# SCH_Nucleo__V3_2022-10-20.net
KiCad netlist of a schematic drawn in EasyEDA
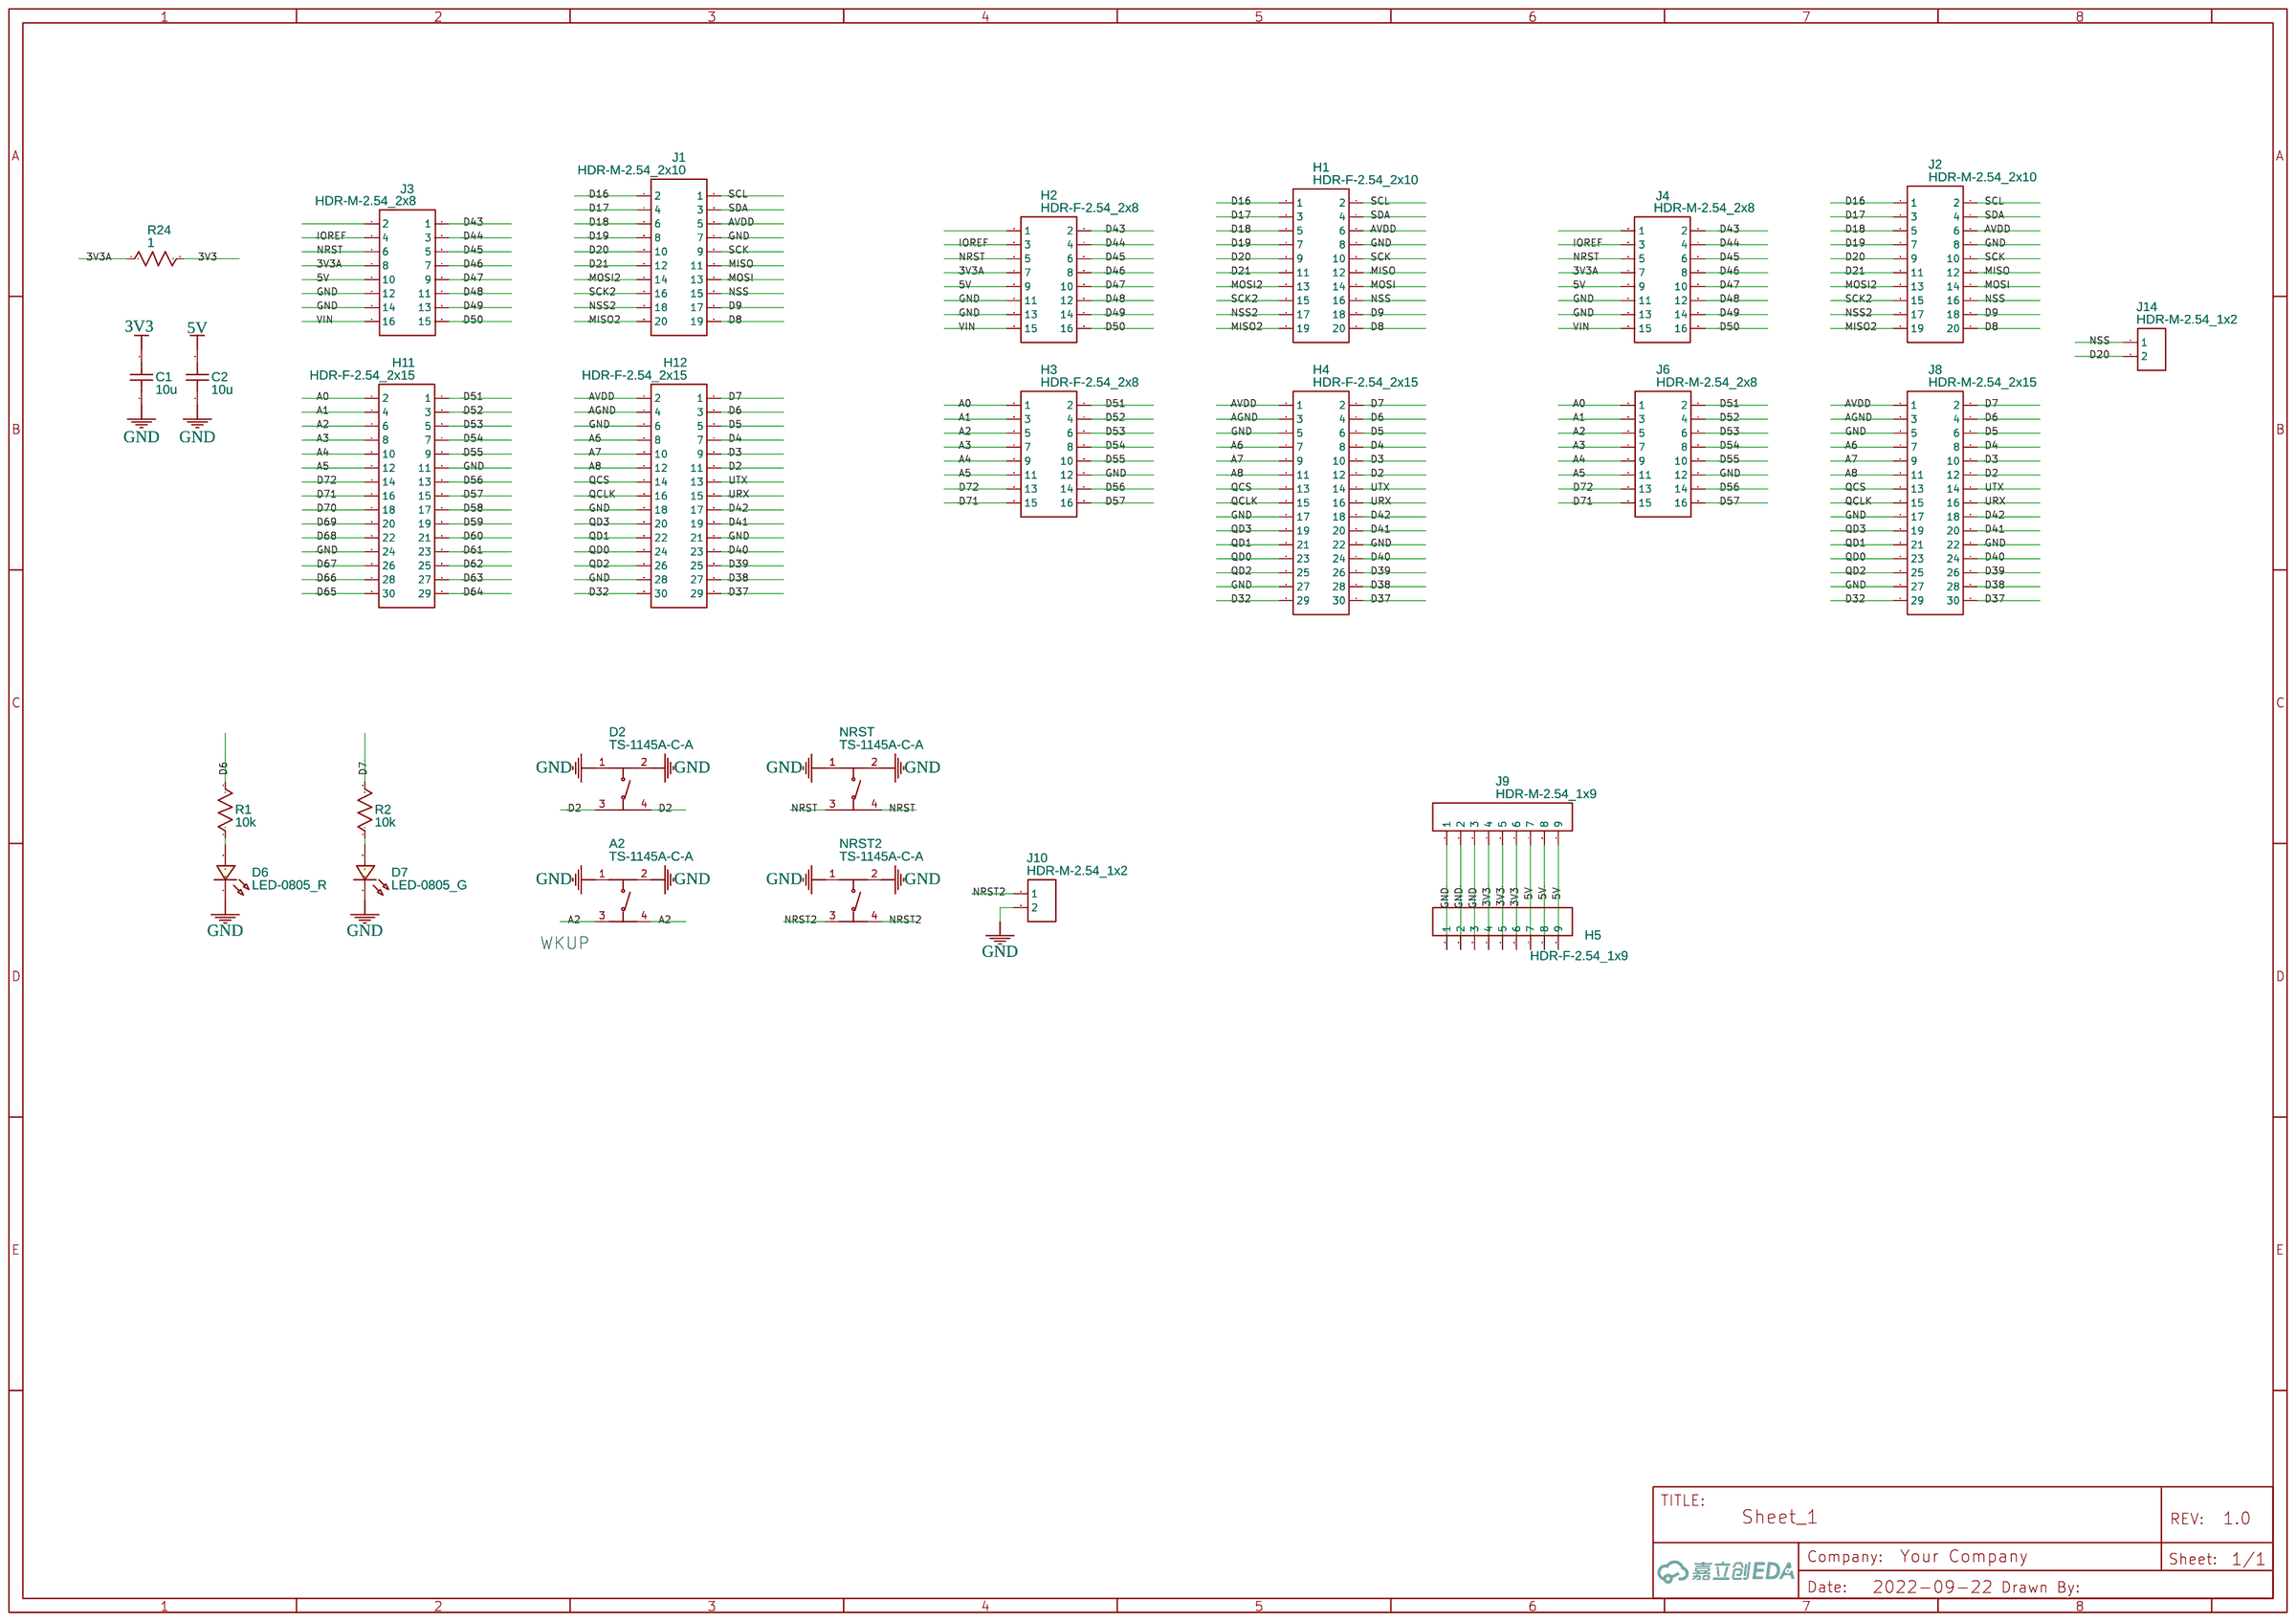
[diagram p0: 连接器]
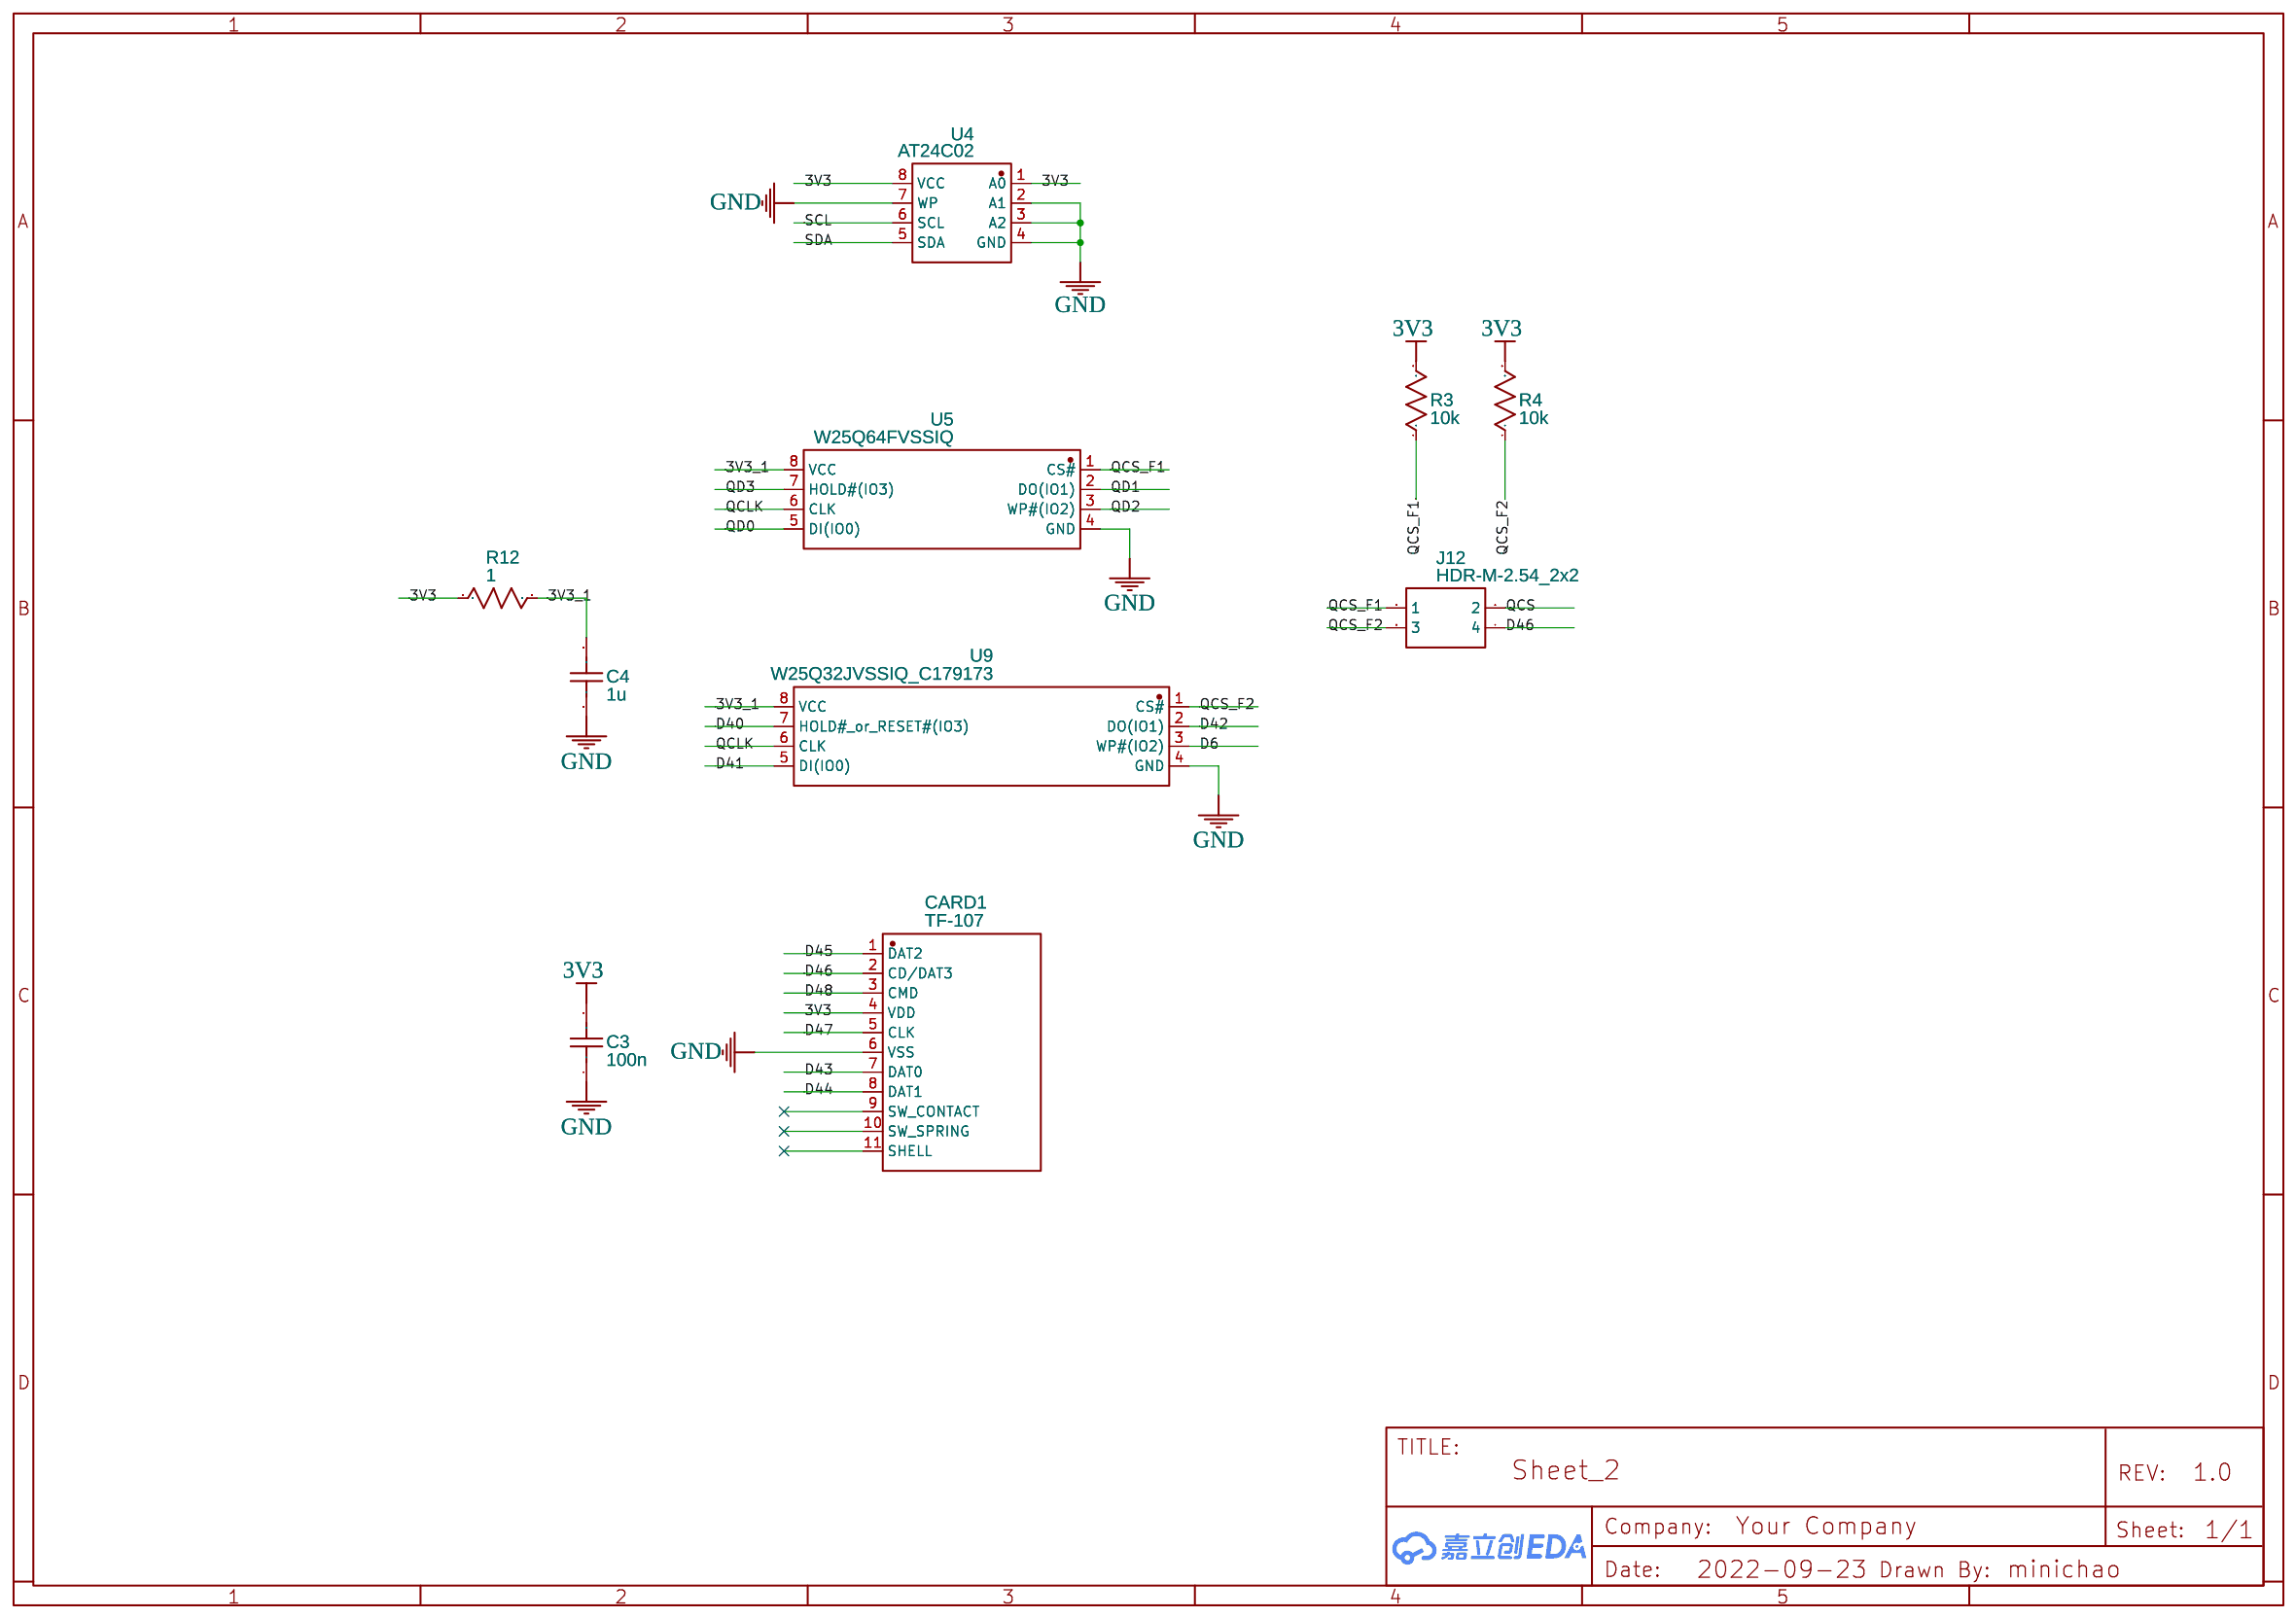
[diagram p1: 存储]
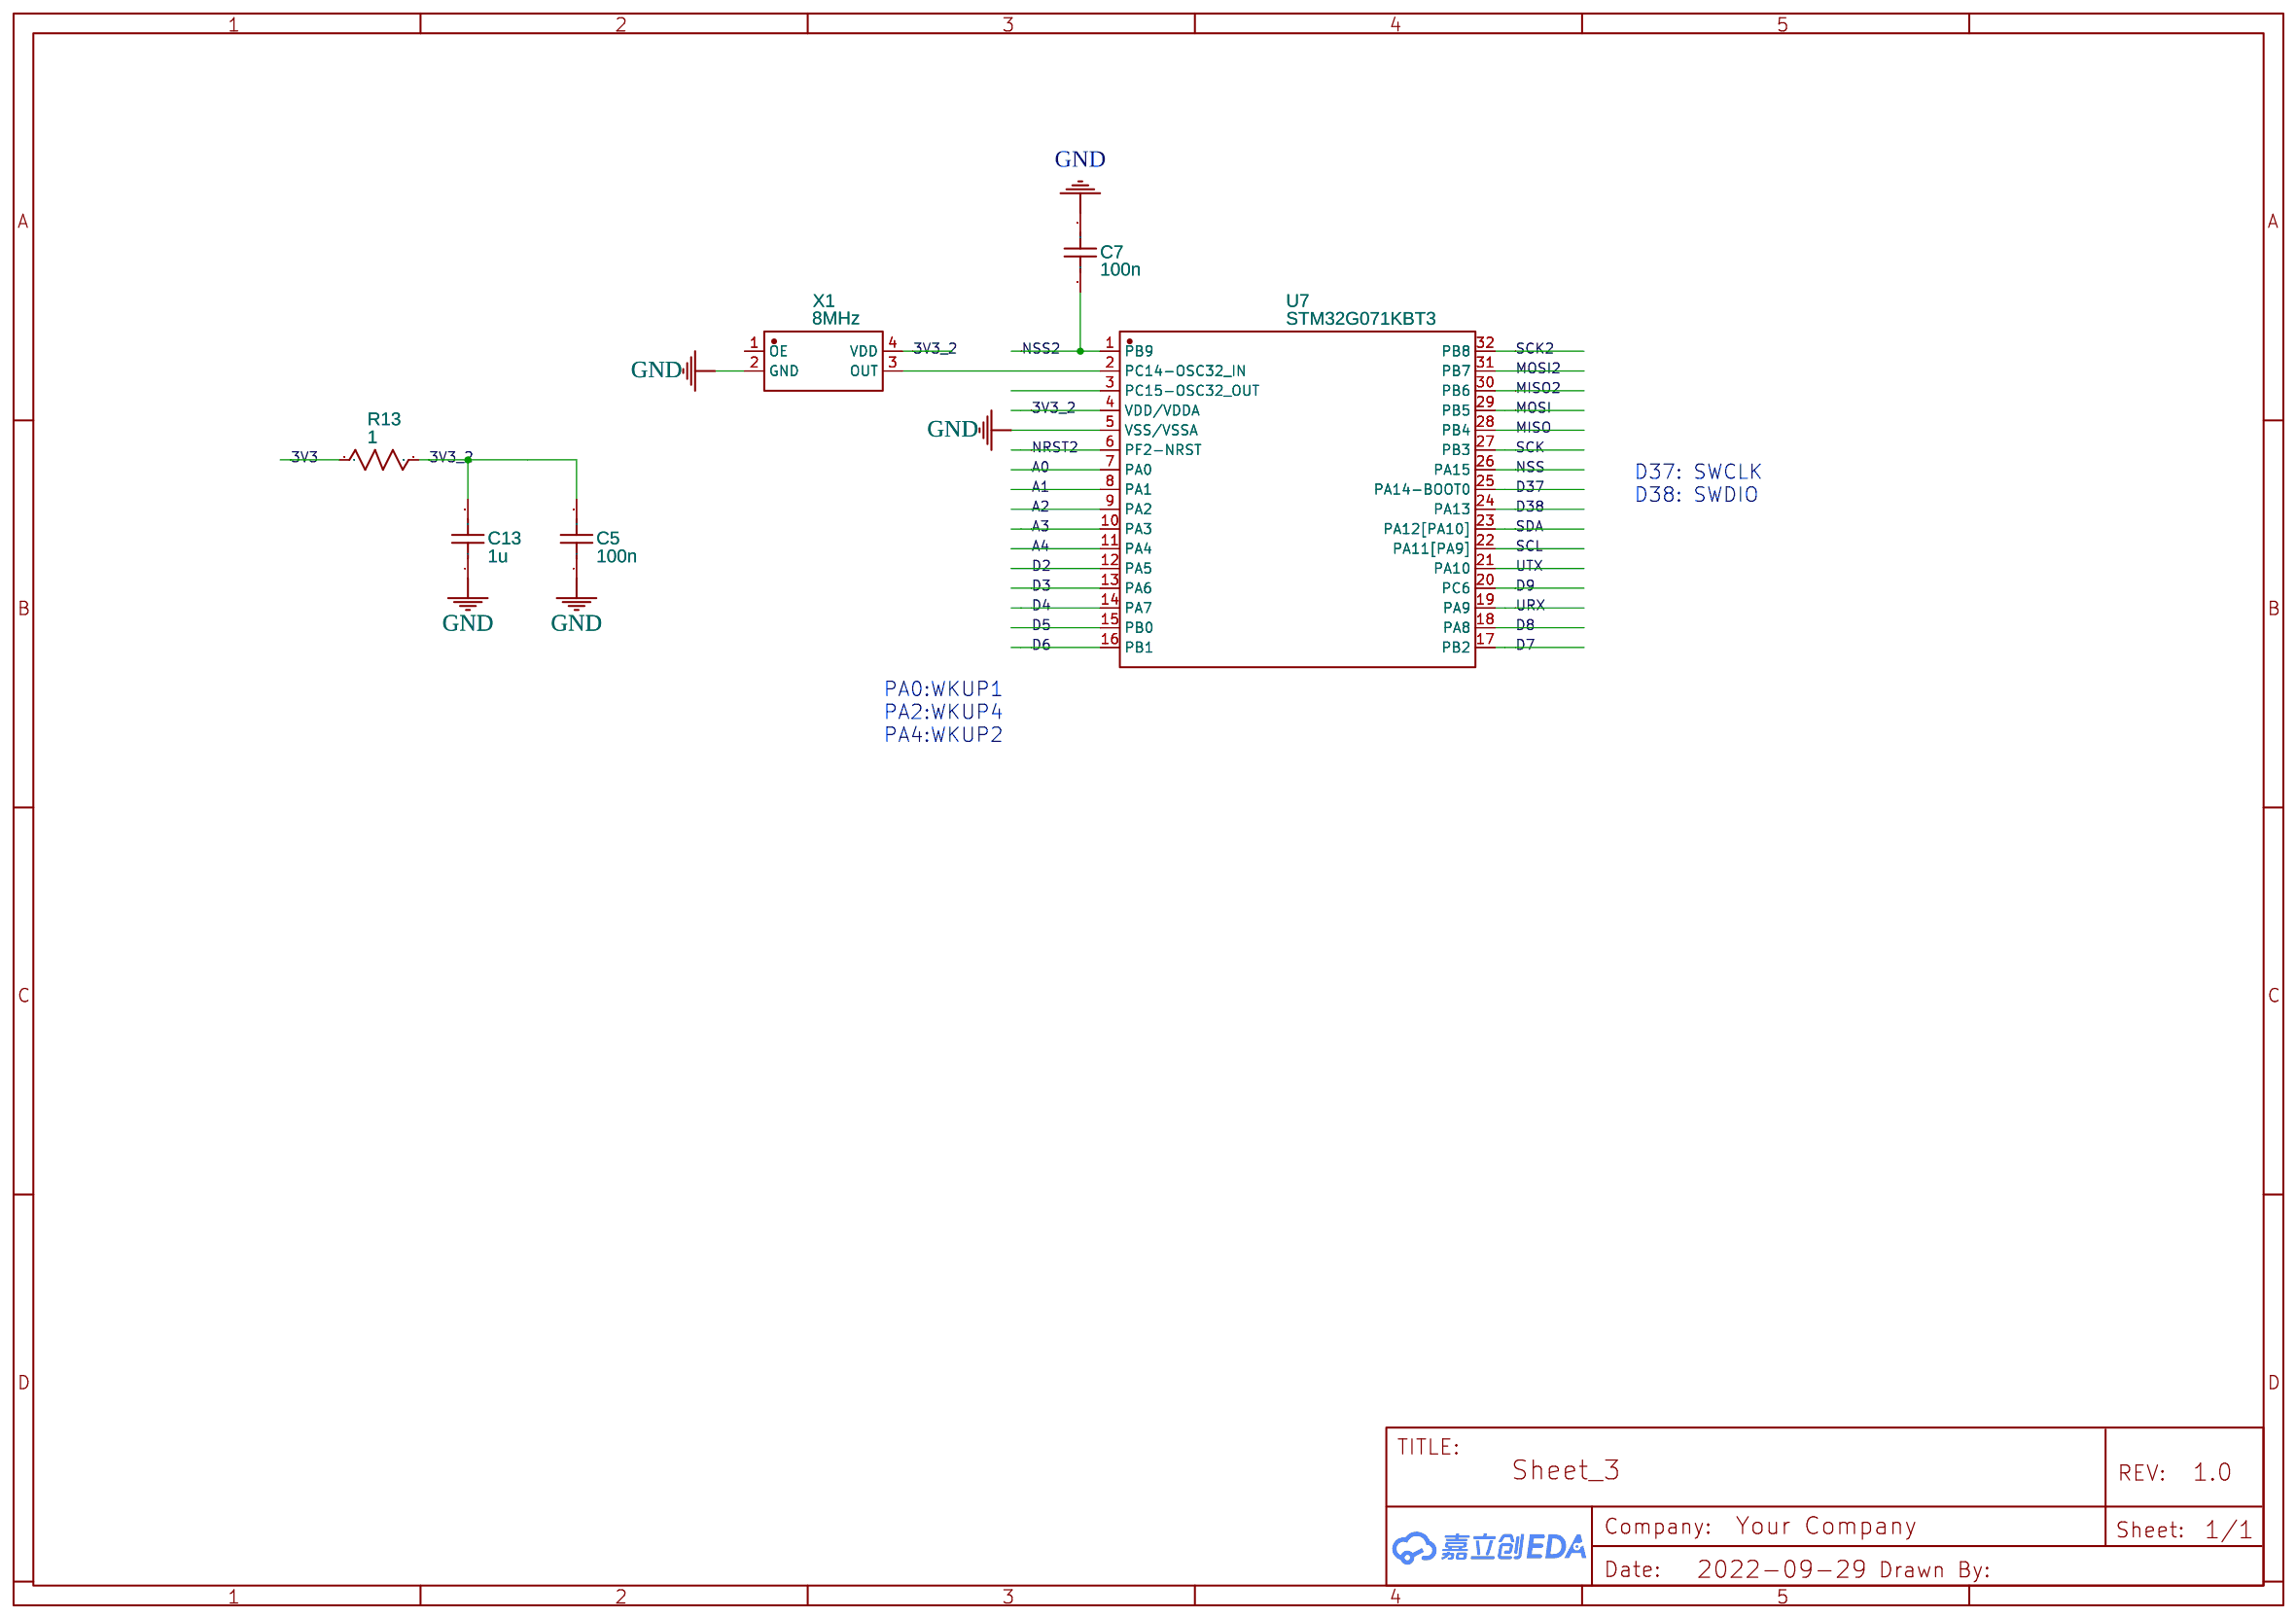
[diagram p2: mcu]
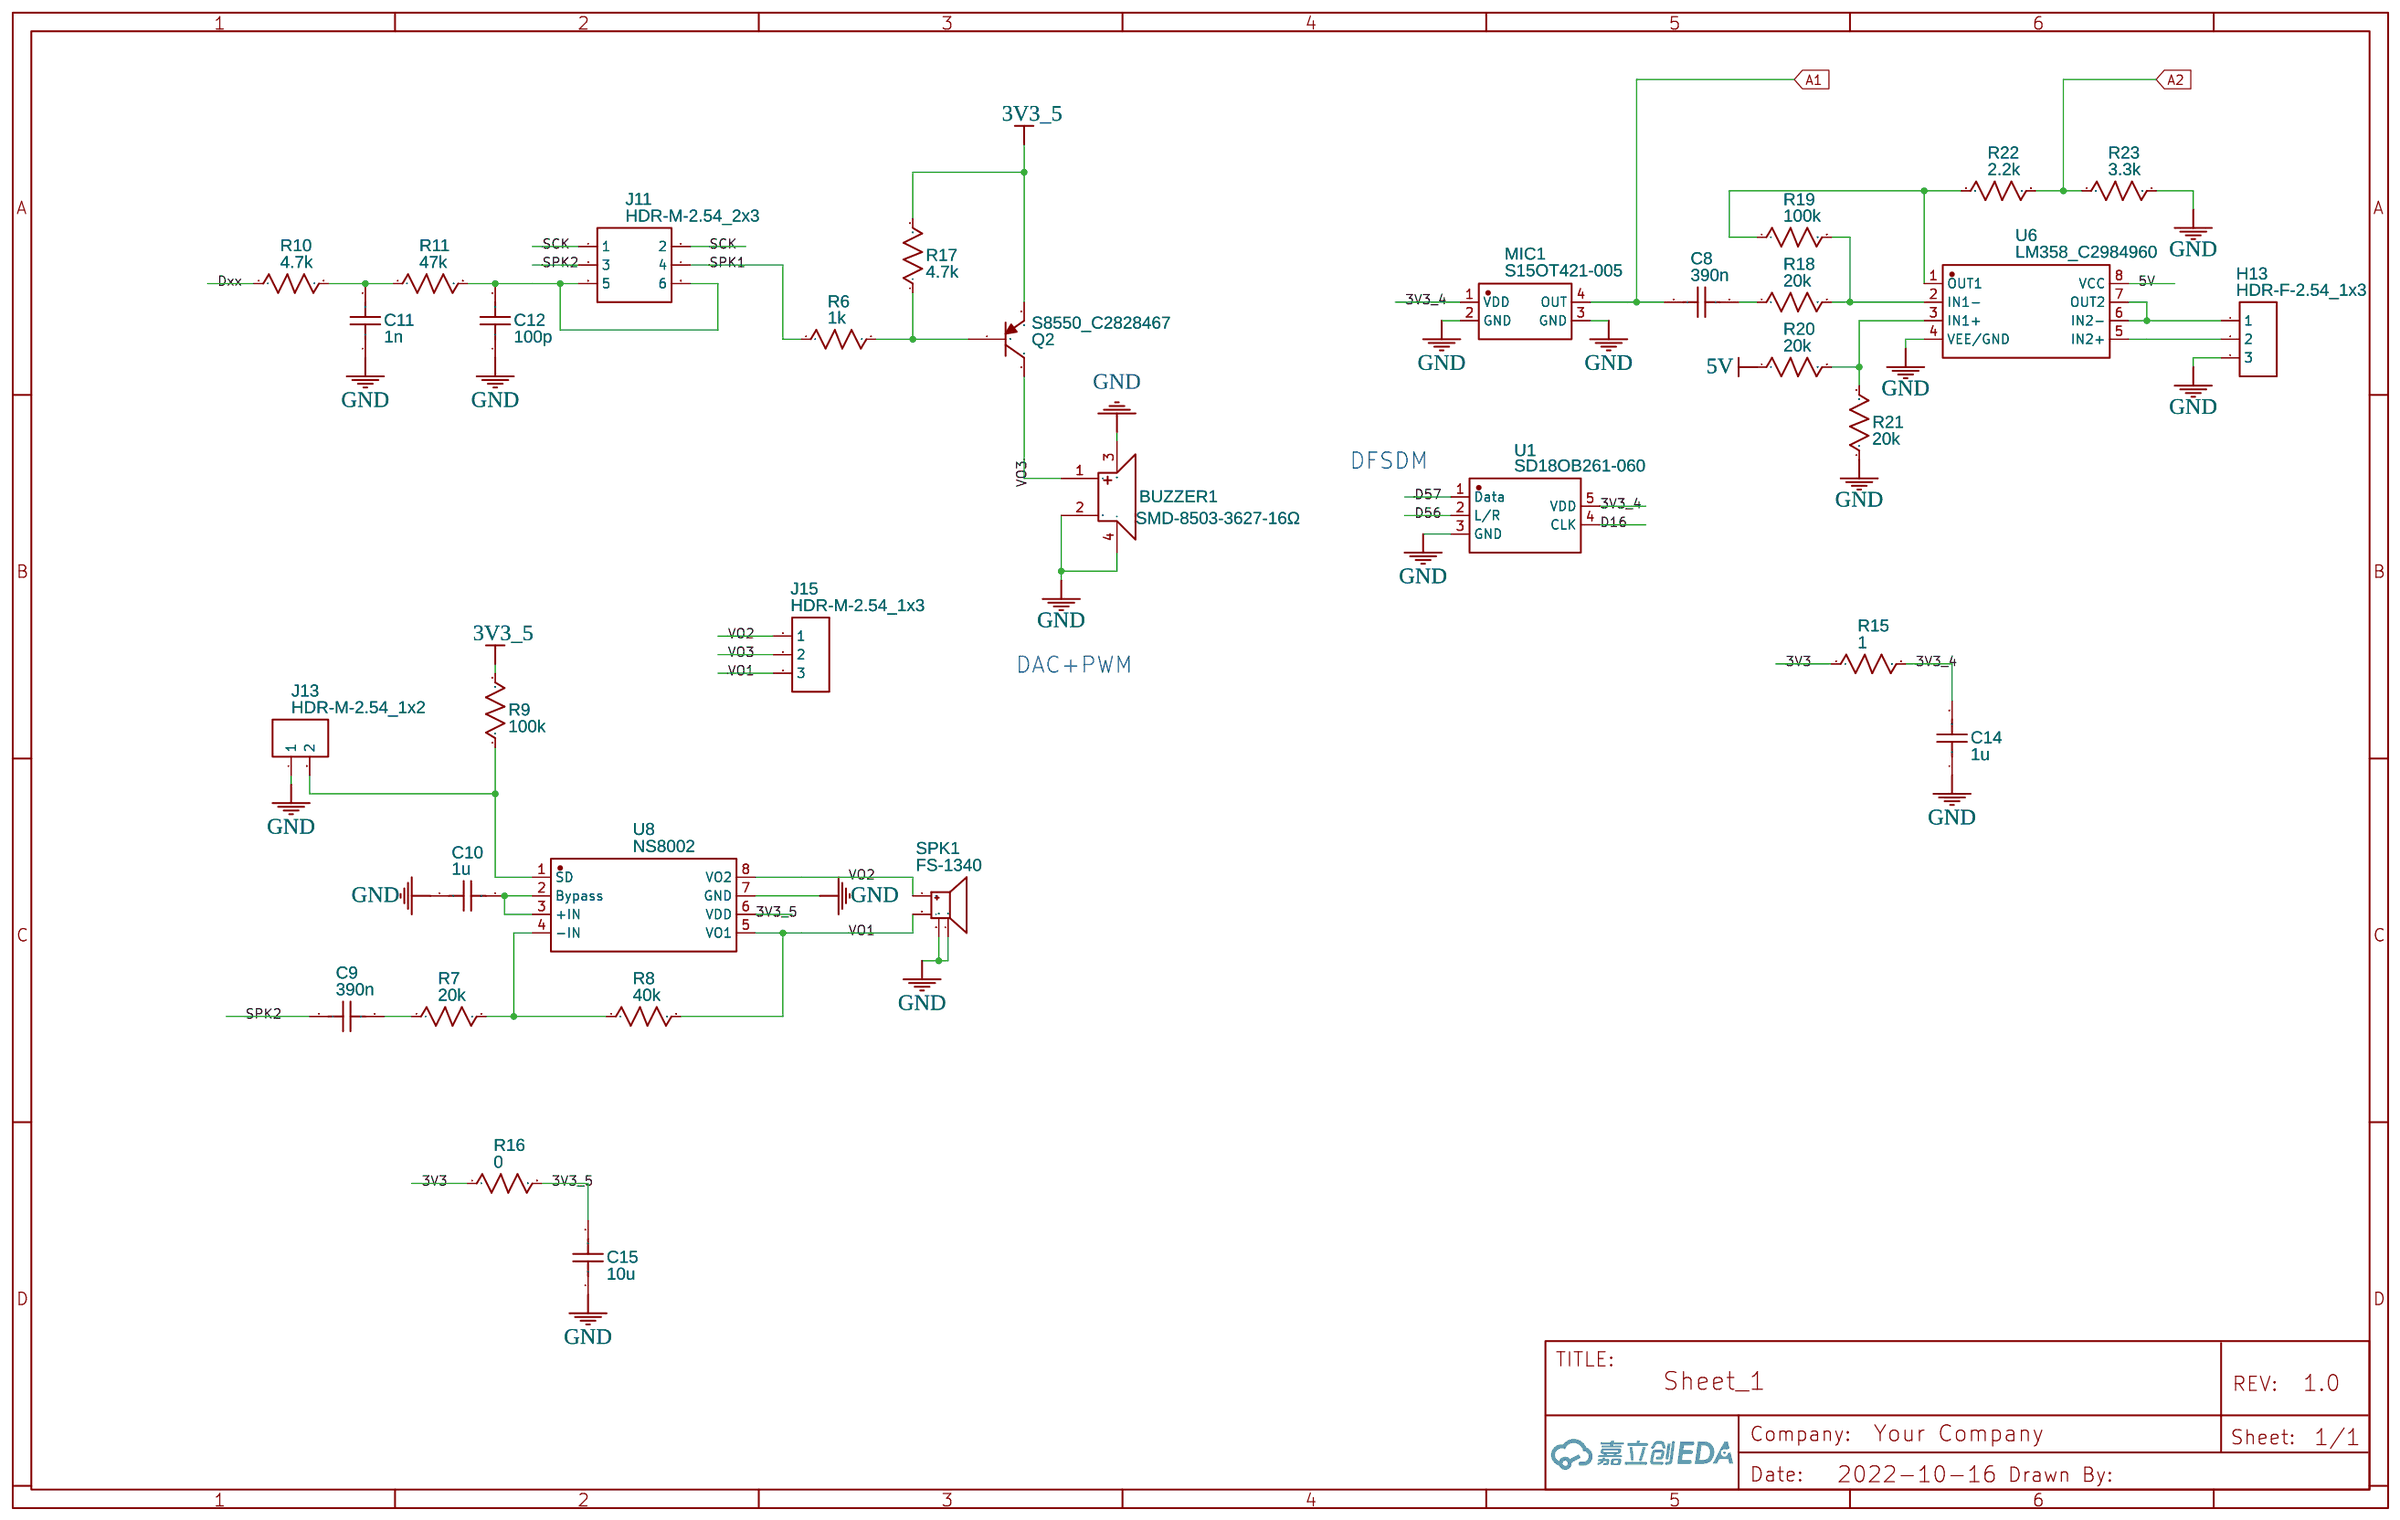
[diagram p3: 音频]
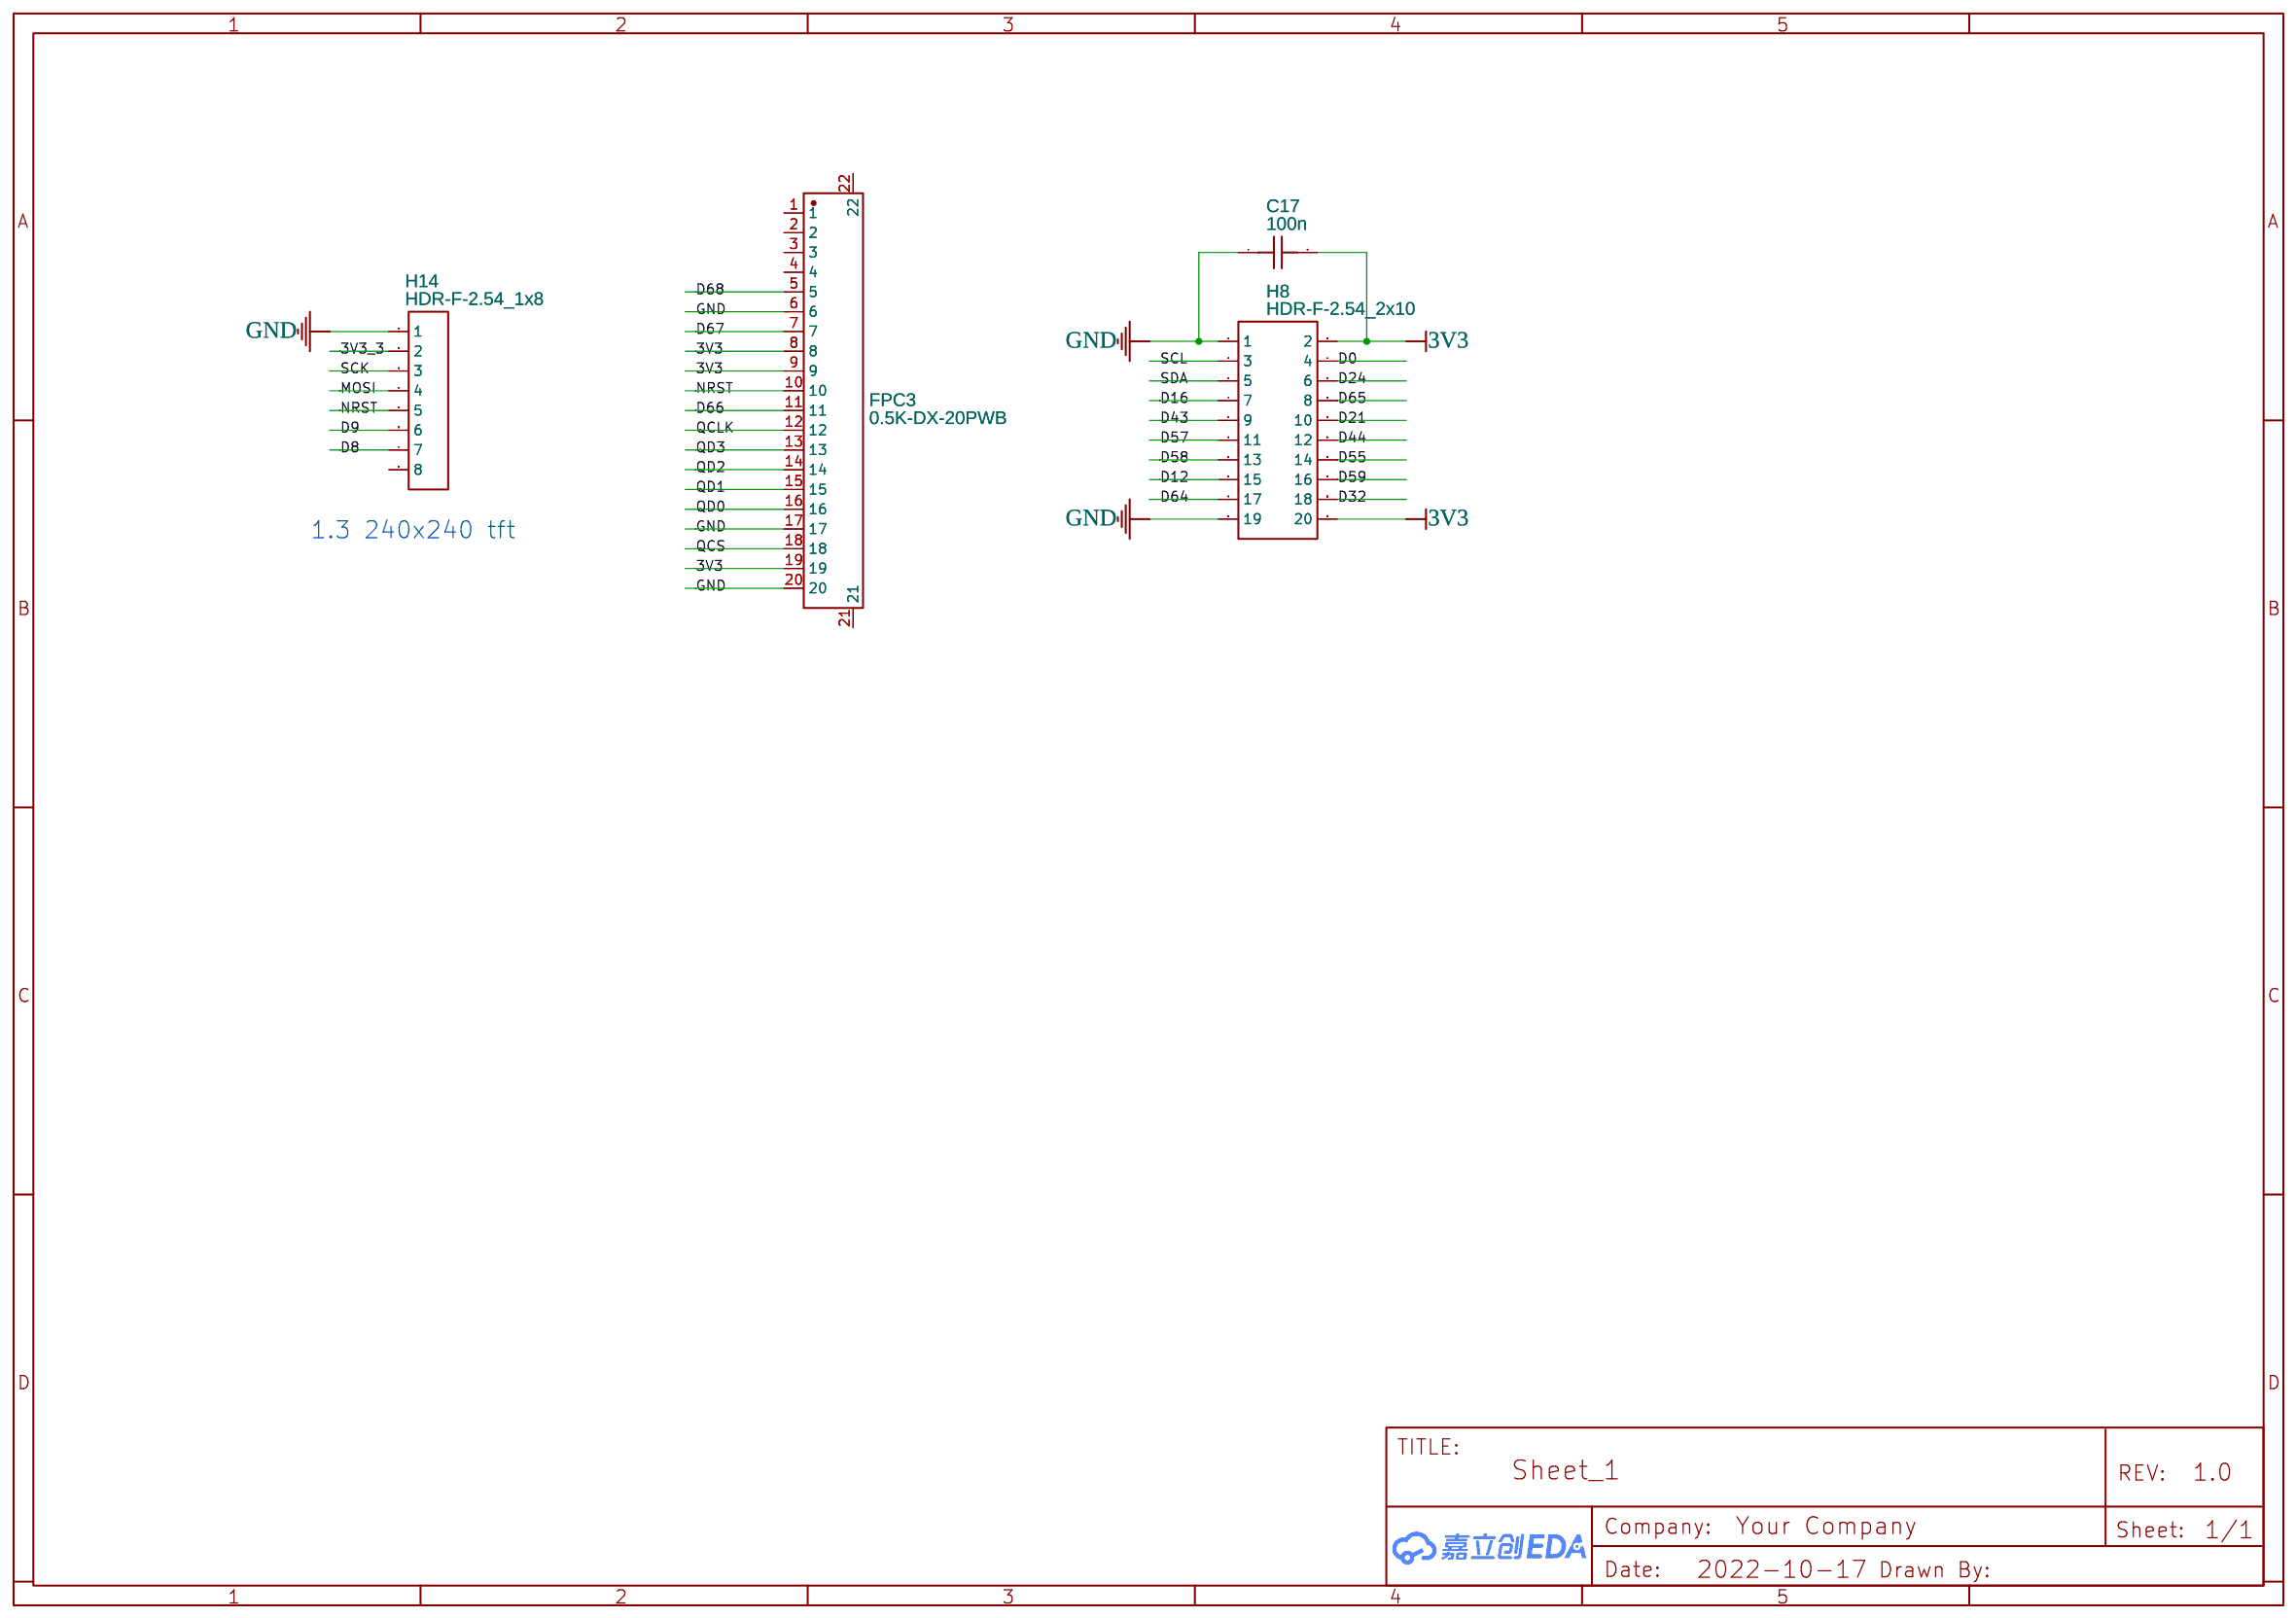
[diagram p4: 显示]
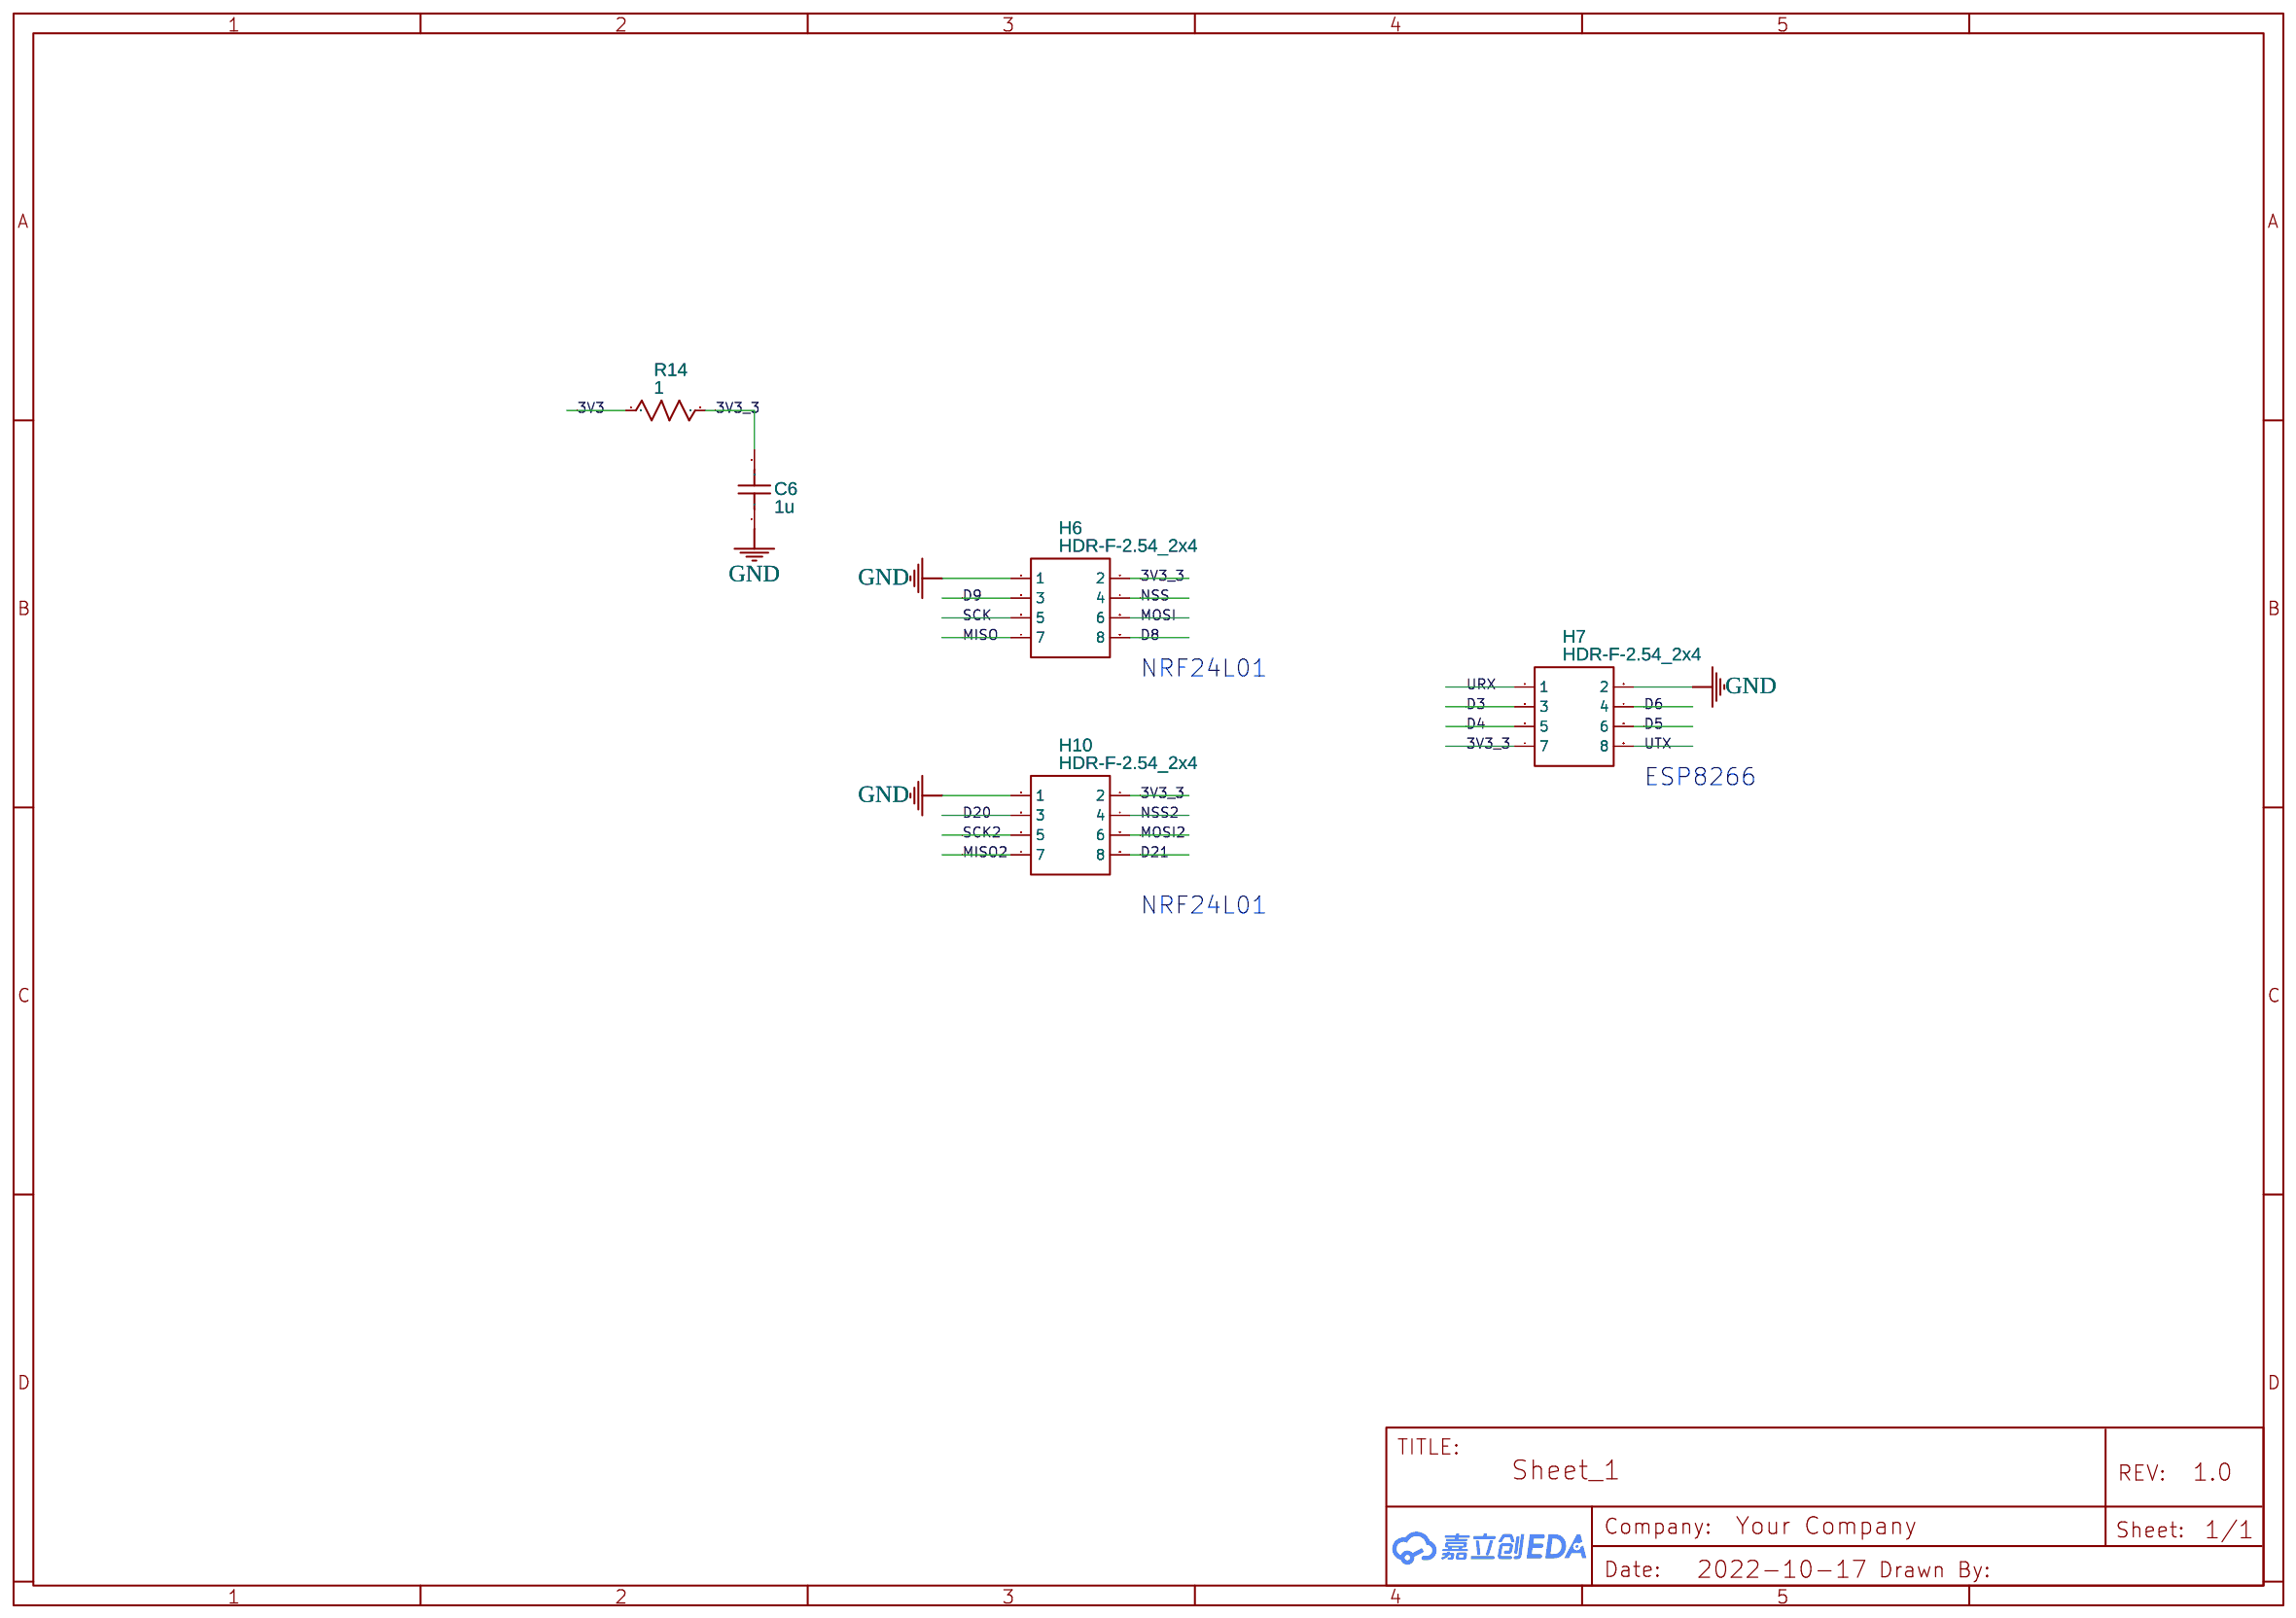
[diagram p5: 无线]
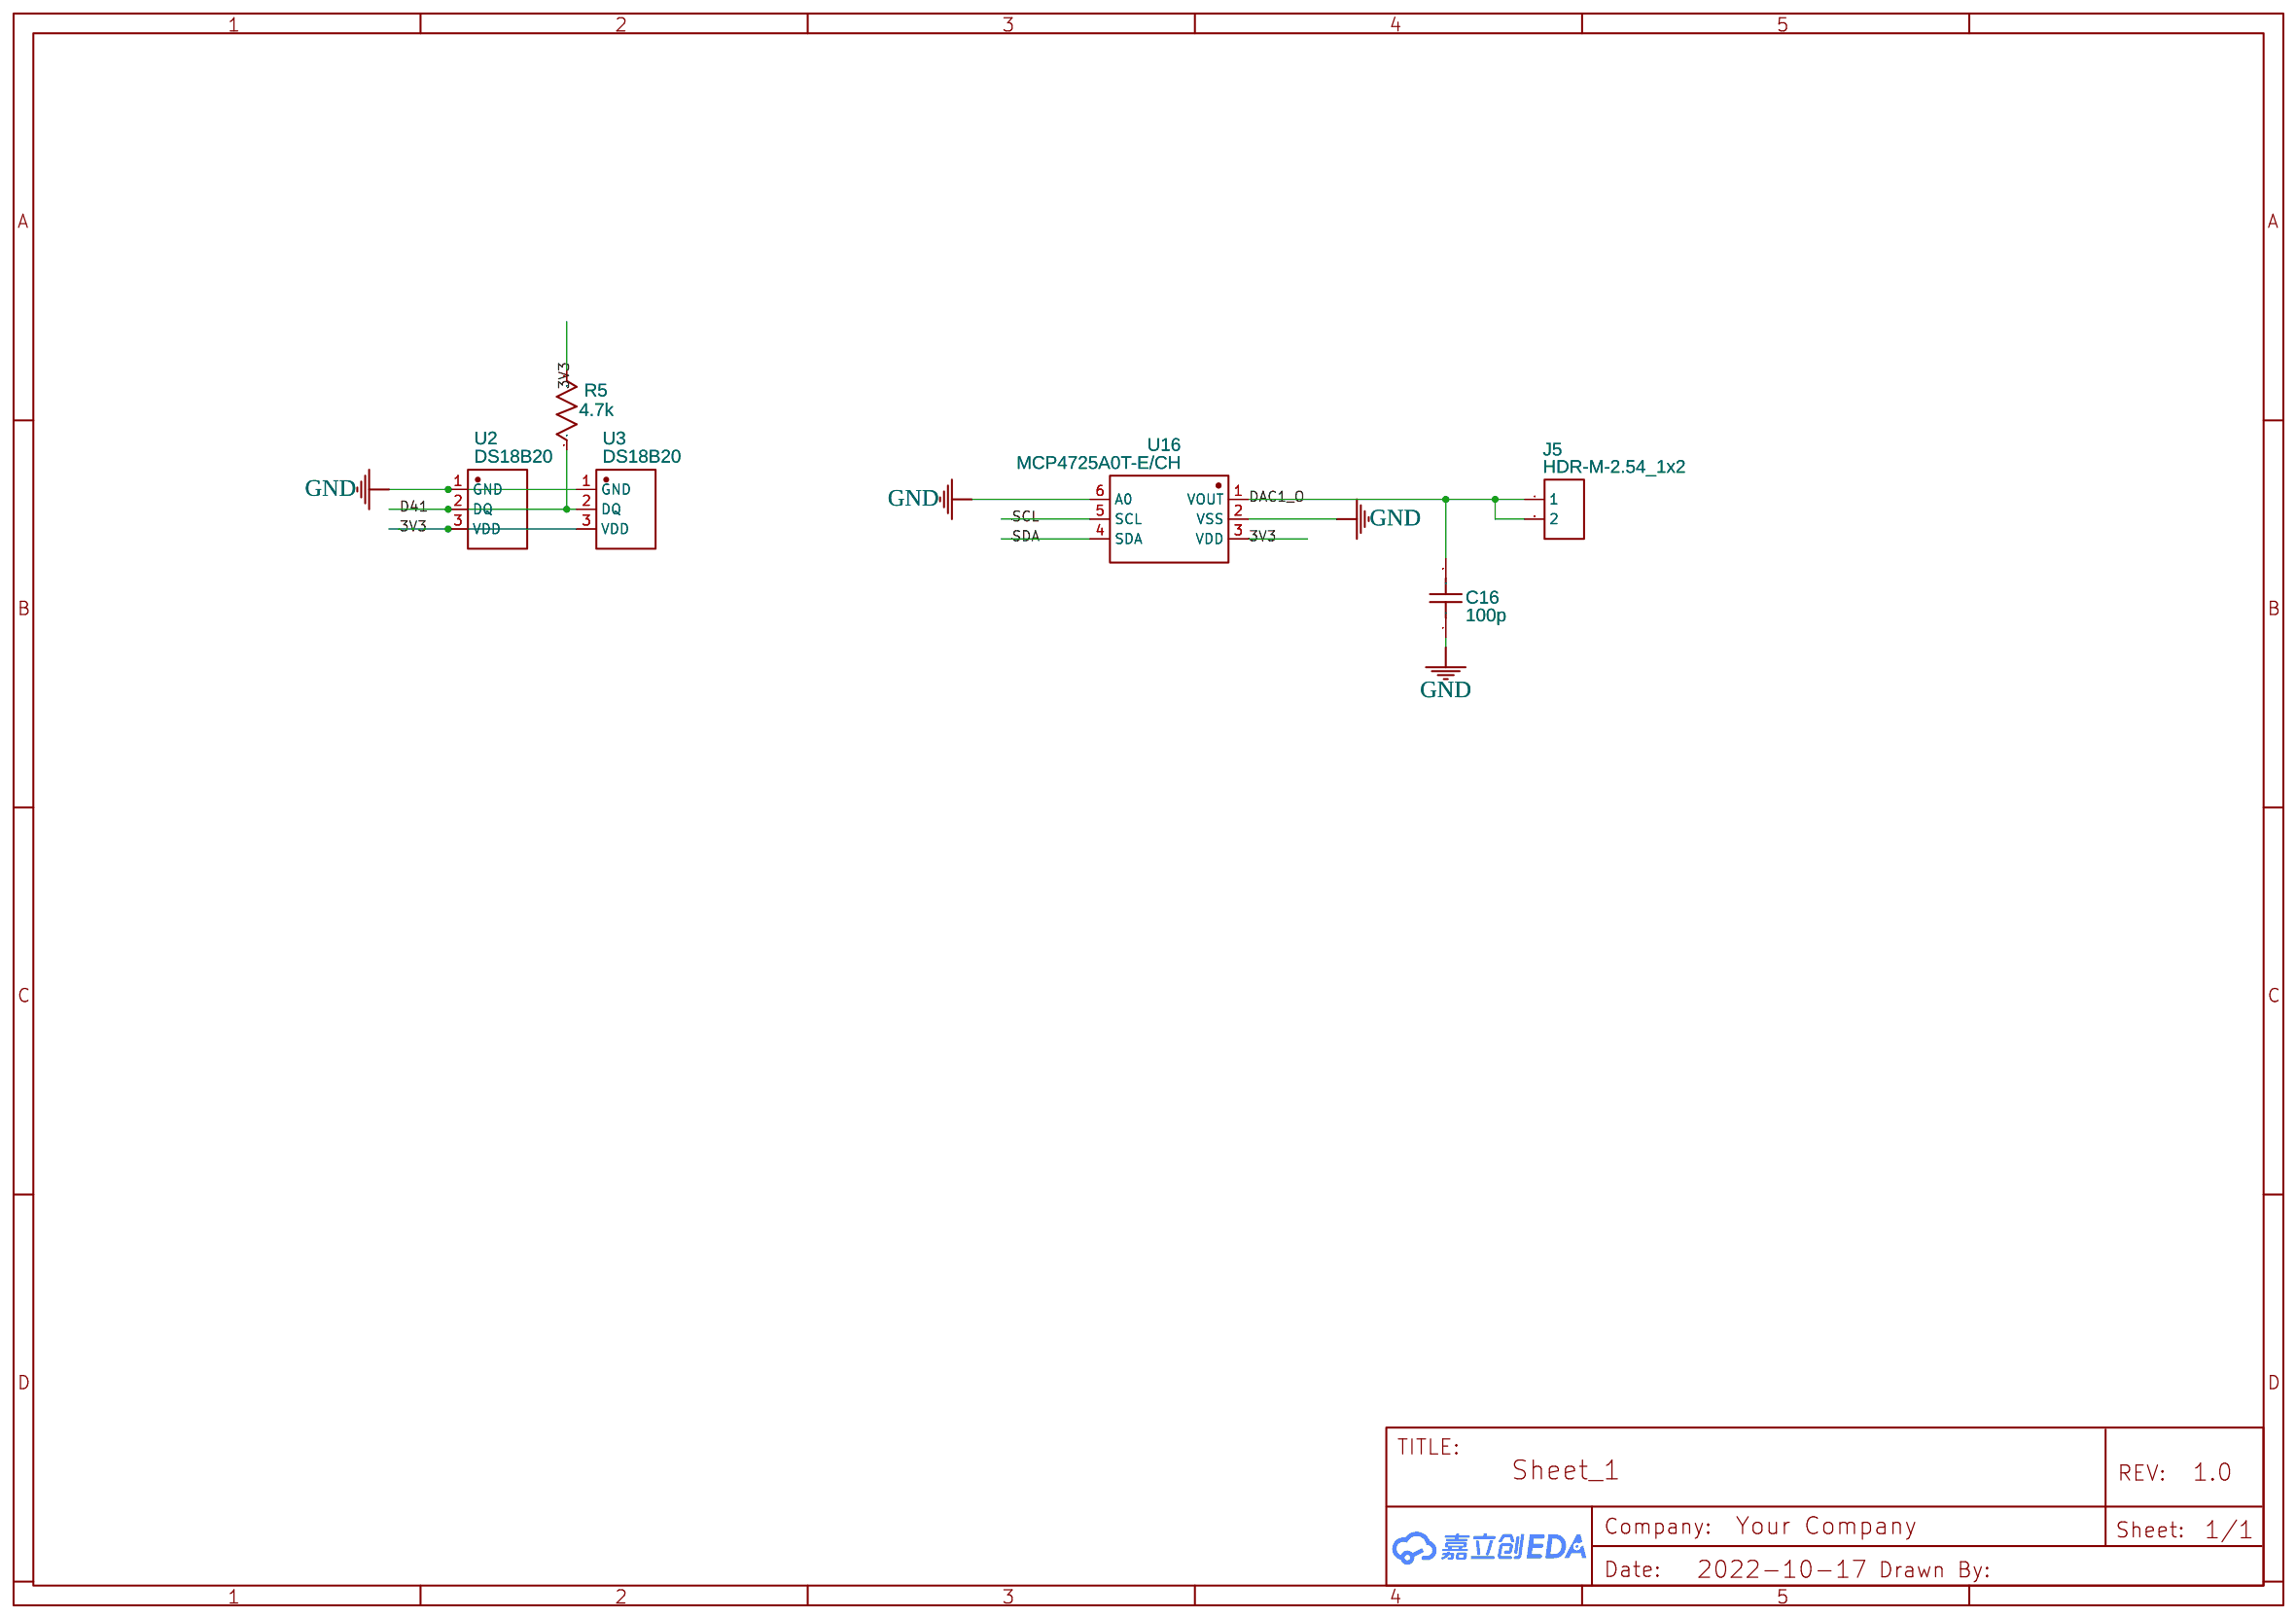
[diagram p6: 小外设模块]

(export (version "E")
  (design (tool "Eeschema 10.0.6"))
  (components
    (comp (ref "A2")
      (value "TS-1145A-C-A")
      (fields (field (name "BOM_Supplier Part") "C318903"))
      (libsource (lib "") (part "TS-1145A-C-A_2"))
    )
    (comp (ref "C1")
      (value "10u")
      (fields
        (field (name "BOM_Manufacturer Part") "0805B105M500NT")
        (field (name "BOM_Supplier Part") "C2913555")
      )
      (libsource (lib "") (part "C_0805_US"))
    )
    (comp (ref "C2")
      (value "10u")
      (fields
        (field (name "BOM_Manufacturer Part") "0805B105M500NT")
        (field (name "BOM_Supplier Part") "C2913555")
      )
      (libsource (lib "") (part "C_0805_US"))
    )
    (comp (ref "D2")
      (value "TS-1145A-C-A")
      (fields (field (name "BOM_Supplier Part") "C318903"))
      (libsource (lib "") (part "TS-1145A-C-A"))
    )
    (comp (ref "D6")
      (value "LED-0805_R")
      (fields
        (field (name "BOM_Manufacturer Part") "17-21SURC/S530-A3/TR8")
        (field (name "BOM_Supplier Part") "C72037")
      )
      (libsource (lib "") (part "LED-0805_R"))
    )
    (comp (ref "D7")
      (value "LED-0805_G")
      (fields (field (name "BOM_Manufacturer Part") "NCD0805G1") (field (name "BOM_Supplier Part") "C84260"))
      (libsource (lib "") (part "LED-0805_G"))
    )
    (comp (ref "H1")
      (value "HDR-F-2.54_2x10")
      (fields (field (name "BOM_Supplier Part") "C30867"))
      (libsource (lib "") (part "HDR-F-2.54_2x10"))
    )
    (comp (ref "H2")
      (value "HDR-F-2.54_2x8")
      (fields (field (name "BOM_Supplier Part") "C30734"))
      (libsource (lib "") (part "HDR-F-2.54_2x8"))
    )
    (comp (ref "H3")
      (value "HDR-F-2.54_2x8")
      (fields (field (name "BOM_Supplier Part") "C30734"))
      (libsource (lib "") (part "HDR-F-2.54_2x8"))
    )
    (comp (ref "H4")
      (value "HDR-F-2.54_2x15")
      (fields (field (name "BOM_Supplier Part") "C169818"))
      (libsource (lib "") (part "HDR-F-2.54_2x15"))
    )
    (comp (ref "H5")
      (value "HDR-F-2.54_1x9")
      (fields (field (name "BOM_Supplier Part") "C124417"))
      (libsource (lib "") (part "HDR-F-2.54_1x9"))
    )
    (comp (ref "H11")
      (value "HDR-F-2.54_2x15")
      (fields (field (name "BOM_Supplier Part") "C169818"))
      (libsource (lib "") (part "HDR-F-2.54_2x15_1"))
    )
    (comp (ref "H12")
      (value "HDR-F-2.54_2x15")
      (fields (field (name "BOM_Supplier Part") "C169818"))
      (libsource (lib "") (part "HDR-F-2.54_2x15_1"))
    )
    (comp (ref "J1")
      (value "HDR-M-2.54_2x10")
      (fields (field (name "BOM_Supplier Part") "C124359"))
      (libsource (lib "") (part "HDR-M-2.54_2x10_1"))
    )
    (comp (ref "J2")
      (value "HDR-M-2.54_2x10")
      (fields (field (name "BOM_Supplier Part") "C124359"))
      (libsource (lib "") (part "HDR-M-2.54_2x10"))
    )
    (comp (ref "J3")
      (value "HDR-M-2.54_2x8")
      (fields (field (name "BOM_Supplier Part") "C68234"))
      (libsource (lib "") (part "HDR-M-2.54_2x8_1"))
    )
    (comp (ref "J4")
      (value "HDR-M-2.54_2x8")
      (fields (field (name "BOM_Supplier Part") "C68234"))
      (libsource (lib "") (part "HDR-M-2.54_2x8_2"))
    )
    (comp (ref "J6")
      (value "HDR-M-2.54_2x8")
      (fields (field (name "BOM_Supplier Part") "C68234"))
      (libsource (lib "") (part "HDR-M-2.54_2x8"))
    )
    (comp (ref "J8")
      (value "HDR-M-2.54_2x15")
      (fields (field (name "BOM_Supplier Part") "C56496"))
      (libsource (lib "") (part "HDR-M-2.54_2x15"))
    )
    (comp (ref "J9")
      (value "HDR-M-2.54_1x9")
      (fields (field (name "BOM_Supplier Part") "C225484"))
      (libsource (lib "") (part "HDR-M-2.54_1x9"))
    )
    (comp (ref "J10")
      (value "HDR-M-2.54_1x2")
      (fields (field (name "BOM_Supplier Part") "C124375"))
      (libsource (lib "") (part "HDR-M-2.54_1x2"))
    )
    (comp (ref "J14")
      (value "HDR-M-2.54_1x2")
      (fields (field (name "BOM_Supplier Part") "C124375"))
      (libsource (lib "") (part "HDR-M-2.54_1x2"))
    )
    (comp (ref "NRST")
      (value "TS-1145A-C-A")
      (fields (field (name "BOM_Supplier Part") "C318903"))
      (libsource (lib "") (part "TS-1145A-C-A_1"))
    )
    (comp (ref "NRST2")
      (value "TS-1145A-C-A")
      (fields (field (name "BOM_Supplier Part") "C318903"))
      (libsource (lib "") (part "TS-1145A-C-A_1"))
    )
    (comp (ref "R1")
      (value "10k")
      (fields
        (field (name "BOM_Manufacturer Part") "TC0525F1001T5E")
        (field (name "BOM_Supplier Part") "C75781")
      )
      (libsource (lib "") (part "R_0805_US_1"))
    )
    (comp (ref "R2")
      (value "10k")
      (fields
        (field (name "BOM_Manufacturer Part") "TC0525F1001T5E")
        (field (name "BOM_Supplier Part") "C75781")
      )
      (libsource (lib "") (part "R_0805_US_1"))
    )
    (comp (ref "R24") (value "1") (libsource (lib "") (part "R_0805_US")))
    (comp (ref "C3")
      (value "100n")
      (fields
        (field (name "BOM_Manufacturer Part") "0805B105M500NT")
        (field (name "BOM_Supplier Part") "C2913555")
      )
      (libsource (lib "") (part "C_0805_US"))
    )
    (comp (ref "C4")
      (value "1u")
      (fields
        (field (name "BOM_Manufacturer Part") "0805B105M500NT")
        (field (name "BOM_Supplier Part") "C2913555")
      )
      (libsource (lib "") (part "C_0805_US"))
    )
    (comp (ref "CARD1")
      (value "TF-107")
      (fields (field (name "BOM_Supplier Part") "C266615"))
      (libsource (lib "") (part "TF-107"))
    )
    (comp (ref "J12")
      (value "HDR-M-2.54_2x2")
      (fields (field (name "BOM_Supplier Part") "C66690"))
      (libsource (lib "") (part "HDR-M-2.54_2x2"))
    )
    (comp (ref "R3") (value "10k") (libsource (lib "") (part "R_0805_US")))
    (comp (ref "R4") (value "10k") (libsource (lib "") (part "R_0805_US")))
    (comp (ref "R12") (value "1") (libsource (lib "") (part "R_0805_US_1")))
    (comp (ref "U4")
      (value "AT24C02")
      (fields (field (name "BOM_Supplier Part") "C688857"))
      (libsource (lib "") (part "AT24C02"))
    )
    (comp (ref "U5")
      (value "W25Q64FVSSIQ")
      (fields (field (name "BOM_Supplier Part") "C2943203"))
      (libsource (lib "") (part "W25Q64FVSSIQ"))
    )
    (comp (ref "U9")
      (value "W25Q32JVSSIQ_C179173")
      (fields
        (field (name "BOM_Manufacturer Part") "W25Q32JVSSIQ")
        (field (name "BOM_Supplier Part") "C179173")
      )
      (libsource (lib "") (part "W25Q32JVSSIQ_C179173"))
    )
    (comp (ref "C5")
      (value "100n")
      (fields
        (field (name "BOM_Manufacturer Part") "0805B105M500NT")
        (field (name "BOM_Supplier Part") "C2913555")
      )
      (libsource (lib "") (part "C_0805_US"))
    )
    (comp (ref "C7") (value "100n") (libsource (lib "") (part "C_0805_US_1")))
    (comp (ref "C13")
      (value "1u")
      (fields
        (field (name "BOM_Manufacturer Part") "0805B105M500NT")
        (field (name "BOM_Supplier Part") "C2913555")
      )
      (libsource (lib "") (part "C_0805_US"))
    )
    (comp (ref "R13") (value "1") (libsource (lib "") (part "R_0805_US")))
    (comp (ref "U7")
      (value "STM32G071KBT3")
      (fields (field (name "BOM_Supplier Part") "C724238"))
      (libsource (lib "") (part "STM32G071KBT3"))
    )
    (comp (ref "X1")
      (value "8MHz")
      (fields
        (field (name "BOM_Manufacturer Part") "S2H008000I3CHE-T")
        (field (name "BOM_Supplier Part") "C253908")
      )
      (libsource (lib "") (part "S2H008000I3CHE-T"))
    )
    (comp (ref "BUZZER1")
      (value "SMD-8503-3627-16Ω")
      (fields (field (name "BOM_Supplier Part") "C2685545"))
      (libsource (lib "") (part "SMD-8503-3627-16Ω"))
    )
    (comp (ref "C8") (value "390n") (libsource (lib "") (part "C_0805_US")))
    (comp (ref "C9") (value "390n") (libsource (lib "") (part "C_0805_US")))
    (comp (ref "C10") (value "1u") (libsource (lib "") (part "C_0805_US_2")))
    (comp (ref "C11") (value "1n") (libsource (lib "") (part "C_0805_US_1")))
    (comp (ref "C12") (value "100p") (libsource (lib "") (part "C_0805_US_1")))
    (comp (ref "C14")
      (value "1u")
      (fields
        (field (name "BOM_Manufacturer Part") "0805B105M500NT")
        (field (name "BOM_Supplier Part") "C2913555")
      )
      (libsource (lib "") (part "C_0805_US_1"))
    )
    (comp (ref "C15")
      (value "10u")
      (fields
        (field (name "BOM_Manufacturer Part") "0805B105M500NT")
        (field (name "BOM_Supplier Part") "C2913555")
      )
      (libsource (lib "") (part "C_0805_US_1"))
    )
    (comp (ref "H13")
      (value "HDR-F-2.54_1x3")
      (fields (field (name "BOM_Supplier Part") "C146690"))
      (libsource (lib "") (part "HDR-F-2.54_1x3"))
    )
    (comp (ref "J11")
      (value "HDR-M-2.54_2x3")
      (fields (field (name "BOM_Supplier Part") "C65114"))
      (libsource (lib "") (part "HDR-M-2.54_2x3"))
    )
    (comp (ref "J13")
      (value "HDR-M-2.54_1x2")
      (fields (field (name "BOM_Supplier Part") "C124375"))
      (libsource (lib "") (part "HDR-M-2.54_1x2"))
    )
    (comp (ref "J15")
      (value "HDR-M-2.54_1x3")
      (fields (field (name "BOM_Supplier Part") "C180248"))
      (libsource (lib "") (part "HDR-M-2.54_1x3"))
    )
    (comp (ref "MIC1")
      (value "S15OT421-005")
      (fields (field (name "BOM_Supplier Part") "C2684419"))
      (libsource (lib "") (part "S15OT421-005"))
    )
    (comp (ref "Q2")
      (value "S8550_C2828467")
      (fields (field (name "BOM_Manufacturer Part") "S8550") (field (name "BOM_Supplier Part") "C2828467"))
      (libsource (lib "") (part "S8550_C2828467"))
    )
    (comp (ref "R6") (value "1k") (libsource (lib "") (part "R_0805_US")))
    (comp (ref "R7") (value "20k") (libsource (lib "") (part "R_0805_US")))
    (comp (ref "R8") (value "40k") (libsource (lib "") (part "R_0805_US")))
    (comp (ref "R9") (value "100k") (libsource (lib "") (part "R_0805_US_1")))
    (comp (ref "R10") (value "4.7k") (libsource (lib "") (part "R_0805_US")))
    (comp (ref "R11") (value "47k") (libsource (lib "") (part "R_0805_US")))
    (comp (ref "R15") (value "1") (libsource (lib "") (part "R_0805_US")))
    (comp (ref "R16") (value "0") (libsource (lib "") (part "R_0805_US")))
    (comp (ref "R17") (value "4.7k") (libsource (lib "") (part "R_0805_US_1")))
    (comp (ref "R18") (value "20k") (libsource (lib "") (part "R_0805_US")))
    (comp (ref "R19") (value "100k") (libsource (lib "") (part "R_0805_US")))
    (comp (ref "R20") (value "20k") (libsource (lib "") (part "R_0805_US")))
    (comp (ref "R21") (value "20k") (libsource (lib "") (part "R_0805_US_1")))
    (comp (ref "R22") (value "2.2k") (libsource (lib "") (part "R_0805_US")))
    (comp (ref "R23") (value "3.3k") (libsource (lib "") (part "R_0805_US")))
    (comp (ref "SPK1")
      (value "FS-1340")
      (fields (field (name "BOM_Supplier Part") "C482342"))
      (libsource (lib "") (part "FS-1340"))
    )
    (comp (ref "U1")
      (value "SD18OB261-060")
      (fields (field (name "BOM_Supplier Part") "C2895290"))
      (libsource (lib "") (part "SD18OB261-060"))
    )
    (comp (ref "U6")
      (value "LM358_C2984960")
      (fields (field (name "BOM_Manufacturer Part") "LM358") (field (name "BOM_Supplier Part") "C2984960"))
      (libsource (lib "") (part "LM358_C2984960"))
    )
    (comp (ref "U8")
      (value "NS8002")
      (fields (field (name "BOM_Supplier Part") "C189960"))
      (libsource (lib "") (part "NS8002"))
    )
    (comp (ref "C17") (value "100n") (libsource (lib "") (part "C_0805_US")))
    (comp (ref "FPC3")
      (value "0.5K-DX-20PWB")
      (fields (field (name "BOM_Supplier Part") "C2911845"))
      (libsource (lib "") (part "0.5K-DX-20PWB"))
    )
    (comp (ref "H8")
      (value "HDR-F-2.54_2x10")
      (fields (field (name "BOM_Supplier Part") "C30867"))
      (libsource (lib "") (part "HDR-F-2.54_2x10"))
    )
    (comp (ref "H14")
      (value "HDR-F-2.54_1x8")
      (fields (field (name "BOM_Supplier Part") "C225505"))
      (libsource (lib "") (part "HDR-F-2.54_1x8"))
    )
    (comp (ref "C6")
      (value "1u")
      (fields
        (field (name "BOM_Manufacturer Part") "0805B105M500NT")
        (field (name "BOM_Supplier Part") "C2913555")
      )
      (libsource (lib "") (part "C_0805_US"))
    )
    (comp (ref "H6")
      (value "HDR-F-2.54_2x4")
      (fields (field (name "BOM_Supplier Part") "C239344"))
      (libsource (lib "") (part "HDR-F-2.54_2x4"))
    )
    (comp (ref "H7")
      (value "HDR-F-2.54_2x4")
      (fields (field (name "BOM_Supplier Part") "C239344"))
      (libsource (lib "") (part "HDR-F-2.54_2x4"))
    )
    (comp (ref "H10")
      (value "HDR-F-2.54_2x4")
      (fields (field (name "BOM_Supplier Part") "C239344"))
      (libsource (lib "") (part "HDR-F-2.54_2x4"))
    )
    (comp (ref "R14") (value "1") (libsource (lib "") (part "R_0805_US")))
    (comp (ref "C16") (value "100p") (libsource (lib "") (part "C_0805_US")))
    (comp (ref "J5")
      (value "HDR-M-2.54_1x2")
      (fields (field (name "BOM_Supplier Part") "C124375"))
      (libsource (lib "") (part "HDR-M-2.54_1x2"))
    )
    (comp (ref "R5") (value "4.7k") (libsource (lib "") (part "R_0805_US")))
    (comp (ref "U2")
      (value "DS18B20")
      (fields (field (name "BOM_Supplier Part") "C376006"))
      (libsource (lib "") (part "DS18B20"))
    )
    (comp (ref "U3")
      (value "DS18B20")
      (fields (field (name "BOM_Supplier Part") "C376006"))
      (libsource (lib "") (part "DS18B20"))
    )
    (comp (ref "U16")
      (value "MCP4725A0T-E/CH")
      (fields (field (name "BOM_Supplier Part") "C144198"))
      (libsource (lib "") (part "MCP4725A0T-E/CH"))
    )
  )
  (nets
    (net (code "1") (name "3V3") (class "Default")
      (node (ref "C1") (pin "2") (pinfunction "2_2") (pintype "unspecified"))
      (node (ref "C17") (pin "2") (pinfunction "2_2") (pintype "unspecified"))
      (node (ref "C3") (pin "2") (pinfunction "2_2") (pintype "unspecified"))
      (node (ref "CARD1") (pin "4") (pinfunction "VDD_4") (pintype "unspecified"))
      (node (ref "FPC3") (pin "19") (pinfunction "19_19") (pintype "unspecified"))
      (node (ref "FPC3") (pin "8") (pinfunction "8_8") (pintype "unspecified"))
      (node (ref "FPC3") (pin "9") (pinfunction "9_9") (pintype "unspecified"))
      (node (ref "H5") (pin "4") (pinfunction "4_4") (pintype "unspecified"))
      (node (ref "H5") (pin "5") (pinfunction "5_5") (pintype "unspecified"))
      (node (ref "H5") (pin "6") (pinfunction "6_6") (pintype "unspecified"))
      (node (ref "H8") (pin "2") (pinfunction "2_2") (pintype "input"))
      (node (ref "H8") (pin "20") (pinfunction "20_20") (pintype "input"))
      (node (ref "J9") (pin "4") (pinfunction "4_4") (pintype "unspecified"))
      (node (ref "J9") (pin "5") (pinfunction "5_5") (pintype "unspecified"))
      (node (ref "J9") (pin "6") (pinfunction "6_6") (pintype "unspecified"))
      (node (ref "R12") (pin "1") (pinfunction "1_1") (pintype "unspecified"))
      (node (ref "R13") (pin "1") (pinfunction "1_1") (pintype "unspecified"))
      (node (ref "R14") (pin "1") (pinfunction "1_1") (pintype "unspecified"))
      (node (ref "R15") (pin "1") (pinfunction "1_1") (pintype "unspecified"))
      (node (ref "R16") (pin "1") (pinfunction "1_1") (pintype "unspecified"))
      (node (ref "R24") (pin "2") (pinfunction "2_2") (pintype "unspecified"))
      (node (ref "R3") (pin "2") (pinfunction "2_2") (pintype "unspecified"))
      (node (ref "R4") (pin "2") (pinfunction "2_2") (pintype "unspecified"))
      (node (ref "R5") (pin "2") (pinfunction "2_2") (pintype "unspecified"))
      (node (ref "U16") (pin "3") (pinfunction "VDD_3") (pintype "unspecified"))
      (node (ref "U2") (pin "3") (pinfunction "VDD_3") (pintype "unspecified"))
      (node (ref "U3") (pin "3") (pinfunction "VDD_3") (pintype "unspecified"))
      (node (ref "U4") (pin "1") (pinfunction "A0_1") (pintype "unspecified"))
      (node (ref "U4") (pin "8") (pinfunction "VCC_8") (pintype "unspecified"))
    )
    (net (code "2") (name "3V3A") (class "Default")
      (node (ref "H2") (pin "7") (pinfunction "7_7") (pintype "input"))
      (node (ref "J3") (pin "8") (pinfunction "8_8") (pintype "input"))
      (node (ref "J4") (pin "7") (pinfunction "7_7") (pintype "input"))
      (node (ref "R24") (pin "1") (pinfunction "1_1") (pintype "unspecified"))
    )
    (net (code "3") (name "3V3_1") (class "Default")
      (node (ref "C4") (pin "2") (pinfunction "2_2") (pintype "unspecified"))
      (node (ref "R12") (pin "2") (pinfunction "2_2") (pintype "unspecified"))
      (node (ref "U5") (pin "8") (pinfunction "VCC_8") (pintype "unspecified"))
      (node (ref "U9") (pin "8") (pinfunction "VCC_8") (pintype "unspecified"))
    )
    (net (code "4") (name "3V3_2") (class "Default")
      (node (ref "C13") (pin "2") (pinfunction "2_2") (pintype "unspecified"))
      (node (ref "C5") (pin "2") (pinfunction "2_2") (pintype "unspecified"))
      (node (ref "R13") (pin "2") (pinfunction "2_2") (pintype "unspecified"))
      (node (ref "U7") (pin "4") (pinfunction "VDD/VDDA_4") (pintype "unspecified"))
      (node (ref "X1") (pin "4") (pinfunction "VDD_4") (pintype "unspecified"))
    )
    (net (code "5") (name "3V3_3") (class "Default")
      (node (ref "C6") (pin "2") (pinfunction "2_2") (pintype "unspecified"))
      (node (ref "H10") (pin "2") (pinfunction "2_2") (pintype "unspecified"))
      (node (ref "H14") (pin "2") (pinfunction "2_2") (pintype "unspecified"))
      (node (ref "H6") (pin "2") (pinfunction "2_2") (pintype "unspecified"))
      (node (ref "H7") (pin "7") (pinfunction "7_7") (pintype "unspecified"))
      (node (ref "R14") (pin "2") (pinfunction "2_2") (pintype "unspecified"))
    )
    (net (code "6") (name "3V3_4") (class "Default")
      (node (ref "C14") (pin "2") (pinfunction "2_2") (pintype "unspecified"))
      (node (ref "MIC1") (pin "1") (pinfunction "VDD_1") (pintype "unspecified"))
      (node (ref "R15") (pin "2") (pinfunction "2_2") (pintype "unspecified"))
      (node (ref "U1") (pin "5") (pinfunction "VDD_5") (pintype "unspecified"))
    )
    (net (code "7") (name "3V3_5") (class "Default")
      (node (ref "C15") (pin "2") (pinfunction "2_2") (pintype "unspecified"))
      (node (ref "Q2") (pin "2") (pinfunction "E_2") (pintype "unspecified"))
      (node (ref "R16") (pin "2") (pinfunction "2_2") (pintype "unspecified"))
      (node (ref "R17") (pin "2") (pinfunction "2_2") (pintype "unspecified"))
      (node (ref "R9") (pin "2") (pinfunction "2_2") (pintype "unspecified"))
      (node (ref "U8") (pin "6") (pinfunction "VDD_6") (pintype "unspecified"))
    )
    (net (code "8") (name "5V") (class "Default")
      (node (ref "C2") (pin "2") (pinfunction "2_2") (pintype "unspecified"))
      (node (ref "H2") (pin "9") (pinfunction "9_9") (pintype "input"))
      (node (ref "H5") (pin "7") (pinfunction "7_7") (pintype "unspecified"))
      (node (ref "H5") (pin "8") (pinfunction "8_8") (pintype "unspecified"))
      (node (ref "H5") (pin "9") (pinfunction "9_9") (pintype "unspecified"))
      (node (ref "J3") (pin "10") (pinfunction "10_10") (pintype "input"))
      (node (ref "J4") (pin "9") (pinfunction "9_9") (pintype "input"))
      (node (ref "J9") (pin "7") (pinfunction "7_7") (pintype "unspecified"))
      (node (ref "J9") (pin "8") (pinfunction "8_8") (pintype "unspecified"))
      (node (ref "J9") (pin "9") (pinfunction "9_9") (pintype "unspecified"))
      (node (ref "R20") (pin "1") (pinfunction "1_1") (pintype "unspecified"))
      (node (ref "U6") (pin "8") (pinfunction "VCC_8") (pintype "unspecified"))
    )
    (net (code "9") (name "A0") (class "Default")
      (node (ref "H11") (pin "2") (pinfunction "2_2") (pintype "input"))
      (node (ref "H3") (pin "1") (pinfunction "1_1") (pintype "input"))
      (node (ref "J6") (pin "1") (pinfunction "1_1") (pintype "input"))
      (node (ref "U7") (pin "7") (pinfunction "PA0_7") (pintype "unspecified"))
    )
    (net (code "10") (name "A1") (class "Default")
      (node (ref "C8") (pin "1") (pinfunction "1_1") (pintype "unspecified"))
      (node (ref "H11") (pin "4") (pinfunction "4_4") (pintype "input"))
      (node (ref "H3") (pin "3") (pinfunction "3_3") (pintype "input"))
      (node (ref "J6") (pin "3") (pinfunction "3_3") (pintype "input"))
      (node (ref "MIC1") (pin "4") (pinfunction "OUT_4") (pintype "unspecified"))
      (node (ref "U7") (pin "8") (pinfunction "PA1_8") (pintype "unspecified"))
    )
    (net (code "11") (name "A2") (class "Default")
      (node (ref "A2") (pin "3") (pinfunction "3_3") (pintype "unspecified"))
      (node (ref "A2") (pin "4") (pinfunction "4_4") (pintype "unspecified"))
      (node (ref "H11") (pin "6") (pinfunction "6_6") (pintype "input"))
      (node (ref "H3") (pin "5") (pinfunction "5_5") (pintype "input"))
      (node (ref "J6") (pin "5") (pinfunction "5_5") (pintype "input"))
      (node (ref "R22") (pin "2") (pinfunction "2_2") (pintype "unspecified"))
      (node (ref "R23") (pin "1") (pinfunction "1_1") (pintype "unspecified"))
      (node (ref "U7") (pin "9") (pinfunction "PA2_9") (pintype "unspecified"))
    )
    (net (code "12") (name "A3") (class "Default")
      (node (ref "H11") (pin "8") (pinfunction "8_8") (pintype "input"))
      (node (ref "H3") (pin "7") (pinfunction "7_7") (pintype "input"))
      (node (ref "J6") (pin "7") (pinfunction "7_7") (pintype "input"))
      (node (ref "U7") (pin "10") (pinfunction "PA3_10") (pintype "unspecified"))
    )
    (net (code "13") (name "A4") (class "Default")
      (node (ref "H11") (pin "10") (pinfunction "10_10") (pintype "input"))
      (node (ref "H3") (pin "9") (pinfunction "9_9") (pintype "input"))
      (node (ref "J6") (pin "9") (pinfunction "9_9") (pintype "input"))
      (node (ref "U7") (pin "11") (pinfunction "PA4_11") (pintype "unspecified"))
    )
    (net (code "14") (name "A5") (class "Default")
      (node (ref "H11") (pin "12") (pinfunction "12_12") (pintype "input"))
      (node (ref "H3") (pin "11") (pinfunction "11_11") (pintype "input"))
      (node (ref "J6") (pin "11") (pinfunction "11_11") (pintype "input"))
    )
    (net (code "15") (name "A6") (class "Default")
      (node (ref "H12") (pin "8") (pinfunction "8_8") (pintype "input"))
      (node (ref "H4") (pin "7") (pinfunction "7_7") (pintype "input"))
      (node (ref "J8") (pin "7") (pinfunction "7_7") (pintype "input"))
    )
    (net (code "16") (name "A7") (class "Default")
      (node (ref "H12") (pin "10") (pinfunction "10_10") (pintype "input"))
      (node (ref "H4") (pin "9") (pinfunction "9_9") (pintype "input"))
      (node (ref "J8") (pin "9") (pinfunction "9_9") (pintype "input"))
    )
    (net (code "17") (name "A8") (class "Default")
      (node (ref "H12") (pin "12") (pinfunction "12_12") (pintype "input"))
      (node (ref "H4") (pin "11") (pinfunction "11_11") (pintype "input"))
      (node (ref "J8") (pin "11") (pinfunction "11_11") (pintype "input"))
    )
    (net (code "18") (name "AGND") (class "Default")
      (node (ref "H12") (pin "4") (pinfunction "4_4") (pintype "input"))
      (node (ref "H4") (pin "3") (pinfunction "3_3") (pintype "input"))
      (node (ref "J8") (pin "3") (pinfunction "3_3") (pintype "input"))
    )
    (net (code "19") (name "AVDD") (class "Default")
      (node (ref "H1") (pin "6") (pinfunction "6_6") (pintype "input"))
      (node (ref "H12") (pin "2") (pinfunction "2_2") (pintype "input"))
      (node (ref "H4") (pin "1") (pinfunction "1_1") (pintype "input"))
      (node (ref "J1") (pin "5") (pinfunction "5_5") (pintype "unspecified"))
      (node (ref "J2") (pin "6") (pinfunction "6_6") (pintype "unspecified"))
      (node (ref "J8") (pin "1") (pinfunction "1_1") (pintype "input"))
    )
    (net (code "20") (name "D0") (class "Default")
      (node (ref "H8") (pin "4") (pinfunction "4_4") (pintype "input"))
    )
    (net (code "21") (name "D2") (class "Default")
      (node (ref "D2") (pin "3") (pinfunction "3_3") (pintype "unspecified"))
      (node (ref "D2") (pin "4") (pinfunction "4_4") (pintype "unspecified"))
      (node (ref "H12") (pin "11") (pinfunction "11_11") (pintype "input"))
      (node (ref "H4") (pin "12") (pinfunction "12_12") (pintype "input"))
      (node (ref "J8") (pin "12") (pinfunction "12_12") (pintype "input"))
      (node (ref "U7") (pin "12") (pinfunction "PA5_12") (pintype "unspecified"))
    )
    (net (code "22") (name "D3") (class "Default")
      (node (ref "H12") (pin "9") (pinfunction "9_9") (pintype "input"))
      (node (ref "H4") (pin "10") (pinfunction "10_10") (pintype "input"))
      (node (ref "H7") (pin "3") (pinfunction "3_3") (pintype "unspecified"))
      (node (ref "J8") (pin "10") (pinfunction "10_10") (pintype "input"))
      (node (ref "U7") (pin "13") (pinfunction "PA6_13") (pintype "unspecified"))
    )
    (net (code "23") (name "D4") (class "Default")
      (node (ref "H12") (pin "7") (pinfunction "7_7") (pintype "input"))
      (node (ref "H4") (pin "8") (pinfunction "8_8") (pintype "input"))
      (node (ref "H7") (pin "5") (pinfunction "5_5") (pintype "unspecified"))
      (node (ref "J8") (pin "8") (pinfunction "8_8") (pintype "input"))
      (node (ref "U7") (pin "14") (pinfunction "PA7_14") (pintype "unspecified"))
    )
    (net (code "24") (name "D5") (class "Default")
      (node (ref "H12") (pin "5") (pinfunction "5_5") (pintype "input"))
      (node (ref "H4") (pin "6") (pinfunction "6_6") (pintype "input"))
      (node (ref "H7") (pin "6") (pinfunction "6_6") (pintype "unspecified"))
      (node (ref "J8") (pin "6") (pinfunction "6_6") (pintype "input"))
      (node (ref "U7") (pin "15") (pinfunction "PB0_15") (pintype "unspecified"))
    )
    (net (code "25") (name "D6") (class "Default")
      (node (ref "H12") (pin "3") (pinfunction "3_3") (pintype "input"))
      (node (ref "H4") (pin "4") (pinfunction "4_4") (pintype "input"))
      (node (ref "H7") (pin "4") (pinfunction "4_4") (pintype "unspecified"))
      (node (ref "J8") (pin "4") (pinfunction "4_4") (pintype "input"))
      (node (ref "R1") (pin "2") (pinfunction "2_2") (pintype "unspecified"))
      (node (ref "U7") (pin "16") (pinfunction "PB1_16") (pintype "unspecified"))
      (node (ref "U9") (pin "3") (pinfunction "WP#(IO2)_3") (pintype "unspecified"))
    )
    (net (code "26") (name "D7") (class "Default")
      (node (ref "H12") (pin "1") (pinfunction "1_1") (pintype "input"))
      (node (ref "H4") (pin "2") (pinfunction "2_2") (pintype "input"))
      (node (ref "J8") (pin "2") (pinfunction "2_2") (pintype "input"))
      (node (ref "R2") (pin "2") (pinfunction "2_2") (pintype "unspecified"))
      (node (ref "U7") (pin "17") (pinfunction "PB2_17") (pintype "unspecified"))
    )
    (net (code "27") (name "D8") (class "Default")
      (node (ref "H1") (pin "20") (pinfunction "20_20") (pintype "input"))
      (node (ref "H14") (pin "7") (pinfunction "7_7") (pintype "unspecified"))
      (node (ref "H6") (pin "8") (pinfunction "8_8") (pintype "unspecified"))
      (node (ref "J1") (pin "19") (pinfunction "19_19") (pintype "unspecified"))
      (node (ref "J2") (pin "20") (pinfunction "20_20") (pintype "unspecified"))
      (node (ref "U7") (pin "18") (pinfunction "PA8_18") (pintype "unspecified"))
    )
    (net (code "28") (name "D9") (class "Default")
      (node (ref "H1") (pin "18") (pinfunction "18_18") (pintype "input"))
      (node (ref "H14") (pin "6") (pinfunction "6_6") (pintype "unspecified"))
      (node (ref "H6") (pin "3") (pinfunction "3_3") (pintype "unspecified"))
      (node (ref "J1") (pin "17") (pinfunction "17_17") (pintype "unspecified"))
      (node (ref "J2") (pin "18") (pinfunction "18_18") (pintype "unspecified"))
      (node (ref "U7") (pin "20") (pinfunction "PC6_20") (pintype "unspecified"))
    )
    (net (code "29") (name "D12") (class "Default")
      (node (ref "H8") (pin "15") (pinfunction "15_15") (pintype "input"))
    )
    (net (code "30") (name "D16") (class "Default")
      (node (ref "H1") (pin "1") (pinfunction "1_1") (pintype "input"))
      (node (ref "H8") (pin "7") (pinfunction "7_7") (pintype "input"))
      (node (ref "J1") (pin "2") (pinfunction "2_2") (pintype "unspecified"))
      (node (ref "J2") (pin "1") (pinfunction "1_1") (pintype "unspecified"))
      (node (ref "U1") (pin "4") (pinfunction "CLK_4") (pintype "unspecified"))
    )
    (net (code "31") (name "D17") (class "Default")
      (node (ref "H1") (pin "3") (pinfunction "3_3") (pintype "input"))
      (node (ref "J1") (pin "4") (pinfunction "4_4") (pintype "unspecified"))
      (node (ref "J2") (pin "3") (pinfunction "3_3") (pintype "unspecified"))
    )
    (net (code "32") (name "D18") (class "Default")
      (node (ref "H1") (pin "5") (pinfunction "5_5") (pintype "input"))
      (node (ref "J1") (pin "6") (pinfunction "6_6") (pintype "unspecified"))
      (node (ref "J2") (pin "5") (pinfunction "5_5") (pintype "unspecified"))
    )
    (net (code "33") (name "D19") (class "Default")
      (node (ref "H1") (pin "7") (pinfunction "7_7") (pintype "input"))
      (node (ref "J1") (pin "8") (pinfunction "8_8") (pintype "unspecified"))
      (node (ref "J2") (pin "7") (pinfunction "7_7") (pintype "unspecified"))
    )
    (net (code "34") (name "D20") (class "Default")
      (node (ref "H1") (pin "9") (pinfunction "9_9") (pintype "input"))
      (node (ref "H10") (pin "3") (pinfunction "3_3") (pintype "unspecified"))
      (node (ref "J1") (pin "10") (pinfunction "10_10") (pintype "unspecified"))
      (node (ref "J14") (pin "2") (pinfunction "2_2") (pintype "unspecified"))
      (node (ref "J2") (pin "9") (pinfunction "9_9") (pintype "unspecified"))
    )
    (net (code "35") (name "D21") (class "Default")
      (node (ref "H1") (pin "11") (pinfunction "11_11") (pintype "input"))
      (node (ref "H10") (pin "8") (pinfunction "8_8") (pintype "unspecified"))
      (node (ref "H8") (pin "10") (pinfunction "10_10") (pintype "input"))
      (node (ref "J1") (pin "12") (pinfunction "12_12") (pintype "unspecified"))
      (node (ref "J2") (pin "11") (pinfunction "11_11") (pintype "unspecified"))
    )
    (net (code "36") (name "D24") (class "Default")
      (node (ref "H8") (pin "6") (pinfunction "6_6") (pintype "input"))
    )
    (net (code "37") (name "D32") (class "Default")
      (node (ref "H12") (pin "30") (pinfunction "30_30") (pintype "input"))
      (node (ref "H4") (pin "29") (pinfunction "29_29") (pintype "input"))
      (node (ref "H8") (pin "18") (pinfunction "18_18") (pintype "input"))
      (node (ref "J8") (pin "29") (pinfunction "29_29") (pintype "input"))
    )
    (net (code "38") (name "D37") (class "Default")
      (node (ref "H12") (pin "29") (pinfunction "29_29") (pintype "input"))
      (node (ref "H4") (pin "30") (pinfunction "30_30") (pintype "input"))
      (node (ref "J8") (pin "30") (pinfunction "30_30") (pintype "input"))
      (node (ref "U7") (pin "25") (pinfunction "PA14-BOOT0_25") (pintype "unspecified"))
    )
    (net (code "39") (name "D38") (class "Default")
      (node (ref "H12") (pin "27") (pinfunction "27_27") (pintype "input"))
      (node (ref "H4") (pin "28") (pinfunction "28_28") (pintype "input"))
      (node (ref "J8") (pin "28") (pinfunction "28_28") (pintype "input"))
      (node (ref "U7") (pin "24") (pinfunction "PA13_24") (pintype "unspecified"))
    )
    (net (code "40") (name "D39") (class "Default")
      (node (ref "H12") (pin "25") (pinfunction "25_25") (pintype "input"))
      (node (ref "H4") (pin "26") (pinfunction "26_26") (pintype "input"))
      (node (ref "J8") (pin "26") (pinfunction "26_26") (pintype "input"))
    )
    (net (code "41") (name "D40") (class "Default")
      (node (ref "H12") (pin "23") (pinfunction "23_23") (pintype "input"))
      (node (ref "H4") (pin "24") (pinfunction "24_24") (pintype "input"))
      (node (ref "J8") (pin "24") (pinfunction "24_24") (pintype "input"))
      (node (ref "U9") (pin "7") (pinfunction "HOLD#_or_RESET#(IO3)_7") (pintype "unspecified"))
    )
    (net (code "42") (name "D41") (class "Default")
      (node (ref "H12") (pin "19") (pinfunction "19_19") (pintype "input"))
      (node (ref "H4") (pin "20") (pinfunction "20_20") (pintype "input"))
      (node (ref "J8") (pin "20") (pinfunction "20_20") (pintype "input"))
      (node (ref "R5") (pin "1") (pinfunction "1_1") (pintype "unspecified"))
      (node (ref "U2") (pin "2") (pinfunction "DQ_2") (pintype "unspecified"))
      (node (ref "U3") (pin "2") (pinfunction "DQ_2") (pintype "unspecified"))
      (node (ref "U9") (pin "5") (pinfunction "DI(IO0)_5") (pintype "unspecified"))
    )
    (net (code "43") (name "D42") (class "Default")
      (node (ref "H12") (pin "17") (pinfunction "17_17") (pintype "input"))
      (node (ref "H4") (pin "18") (pinfunction "18_18") (pintype "input"))
      (node (ref "J8") (pin "18") (pinfunction "18_18") (pintype "input"))
      (node (ref "U9") (pin "2") (pinfunction "DO(IO1)_2") (pintype "unspecified"))
    )
    (net (code "44") (name "D43") (class "Default")
      (node (ref "CARD1") (pin "7") (pinfunction "DAT0_7") (pintype "unspecified"))
      (node (ref "H2") (pin "2") (pinfunction "2_2") (pintype "input"))
      (node (ref "H8") (pin "9") (pinfunction "9_9") (pintype "input"))
      (node (ref "J3") (pin "1") (pinfunction "1_1") (pintype "input"))
      (node (ref "J4") (pin "2") (pinfunction "2_2") (pintype "input"))
    )
    (net (code "45") (name "D44") (class "Default")
      (node (ref "CARD1") (pin "8") (pinfunction "DAT1_8") (pintype "unspecified"))
      (node (ref "H2") (pin "4") (pinfunction "4_4") (pintype "input"))
      (node (ref "H8") (pin "12") (pinfunction "12_12") (pintype "input"))
      (node (ref "J3") (pin "3") (pinfunction "3_3") (pintype "input"))
      (node (ref "J4") (pin "4") (pinfunction "4_4") (pintype "input"))
    )
    (net (code "46") (name "D45") (class "Default")
      (node (ref "CARD1") (pin "1") (pinfunction "DAT2_1") (pintype "unspecified"))
      (node (ref "H2") (pin "6") (pinfunction "6_6") (pintype "input"))
      (node (ref "J3") (pin "5") (pinfunction "5_5") (pintype "input"))
      (node (ref "J4") (pin "6") (pinfunction "6_6") (pintype "input"))
    )
    (net (code "47") (name "D46") (class "Default")
      (node (ref "CARD1") (pin "2") (pinfunction "CD/DAT3_2") (pintype "unspecified"))
      (node (ref "H2") (pin "8") (pinfunction "8_8") (pintype "input"))
      (node (ref "J12") (pin "4") (pinfunction "4_4") (pintype "input"))
      (node (ref "J3") (pin "7") (pinfunction "7_7") (pintype "input"))
      (node (ref "J4") (pin "8") (pinfunction "8_8") (pintype "input"))
    )
    (net (code "48") (name "D47") (class "Default")
      (node (ref "CARD1") (pin "5") (pinfunction "CLK_5") (pintype "unspecified"))
      (node (ref "H2") (pin "10") (pinfunction "10_10") (pintype "input"))
      (node (ref "J3") (pin "9") (pinfunction "9_9") (pintype "input"))
      (node (ref "J4") (pin "10") (pinfunction "10_10") (pintype "input"))
    )
    (net (code "49") (name "D48") (class "Default")
      (node (ref "CARD1") (pin "3") (pinfunction "CMD_3") (pintype "unspecified"))
      (node (ref "H2") (pin "12") (pinfunction "12_12") (pintype "input"))
      (node (ref "J3") (pin "11") (pinfunction "11_11") (pintype "input"))
      (node (ref "J4") (pin "12") (pinfunction "12_12") (pintype "input"))
    )
    (net (code "50") (name "D49") (class "Default")
      (node (ref "H2") (pin "14") (pinfunction "14_14") (pintype "input"))
      (node (ref "J3") (pin "13") (pinfunction "13_13") (pintype "input"))
      (node (ref "J4") (pin "14") (pinfunction "14_14") (pintype "input"))
    )
    (net (code "51") (name "D50") (class "Default")
      (node (ref "H2") (pin "16") (pinfunction "16_16") (pintype "input"))
      (node (ref "J3") (pin "15") (pinfunction "15_15") (pintype "input"))
      (node (ref "J4") (pin "16") (pinfunction "16_16") (pintype "input"))
    )
    (net (code "52") (name "D51") (class "Default")
      (node (ref "H11") (pin "1") (pinfunction "1_1") (pintype "input"))
      (node (ref "H3") (pin "2") (pinfunction "2_2") (pintype "input"))
      (node (ref "J6") (pin "2") (pinfunction "2_2") (pintype "input"))
    )
    (net (code "53") (name "D52") (class "Default")
      (node (ref "H11") (pin "3") (pinfunction "3_3") (pintype "input"))
      (node (ref "H3") (pin "4") (pinfunction "4_4") (pintype "input"))
      (node (ref "J6") (pin "4") (pinfunction "4_4") (pintype "input"))
    )
    (net (code "54") (name "D53") (class "Default")
      (node (ref "H11") (pin "5") (pinfunction "5_5") (pintype "input"))
      (node (ref "H3") (pin "6") (pinfunction "6_6") (pintype "input"))
      (node (ref "J6") (pin "6") (pinfunction "6_6") (pintype "input"))
    )
    (net (code "55") (name "D54") (class "Default")
      (node (ref "H11") (pin "7") (pinfunction "7_7") (pintype "input"))
      (node (ref "H3") (pin "8") (pinfunction "8_8") (pintype "input"))
      (node (ref "J6") (pin "8") (pinfunction "8_8") (pintype "input"))
    )
    (net (code "56") (name "D55") (class "Default")
      (node (ref "H11") (pin "9") (pinfunction "9_9") (pintype "input"))
      (node (ref "H3") (pin "10") (pinfunction "10_10") (pintype "input"))
      (node (ref "H8") (pin "14") (pinfunction "14_14") (pintype "input"))
      (node (ref "J6") (pin "10") (pinfunction "10_10") (pintype "input"))
    )
    (net (code "57") (name "D56") (class "Default")
      (node (ref "H11") (pin "13") (pinfunction "13_13") (pintype "input"))
      (node (ref "H3") (pin "14") (pinfunction "14_14") (pintype "input"))
      (node (ref "J6") (pin "14") (pinfunction "14_14") (pintype "input"))
      (node (ref "U1") (pin "2") (pinfunction "L/R_2") (pintype "unspecified"))
    )
    (net (code "58") (name "D57") (class "Default")
      (node (ref "H11") (pin "15") (pinfunction "15_15") (pintype "input"))
      (node (ref "H3") (pin "16") (pinfunction "16_16") (pintype "input"))
      (node (ref "H8") (pin "11") (pinfunction "11_11") (pintype "input"))
      (node (ref "J6") (pin "16") (pinfunction "16_16") (pintype "input"))
      (node (ref "U1") (pin "1") (pinfunction "Data_1") (pintype "unspecified"))
    )
    (net (code "59") (name "D58") (class "Default")
      (node (ref "H11") (pin "17") (pinfunction "17_17") (pintype "input"))
      (node (ref "H8") (pin "13") (pinfunction "13_13") (pintype "input"))
    )
    (net (code "60") (name "D59") (class "Default")
      (node (ref "H11") (pin "19") (pinfunction "19_19") (pintype "input"))
      (node (ref "H8") (pin "16") (pinfunction "16_16") (pintype "input"))
    )
    (net (code "61") (name "D60") (class "Default")
      (node (ref "H11") (pin "21") (pinfunction "21_21") (pintype "input"))
    )
    (net (code "62") (name "D61") (class "Default")
      (node (ref "H11") (pin "23") (pinfunction "23_23") (pintype "input"))
    )
    (net (code "63") (name "D62") (class "Default")
      (node (ref "H11") (pin "25") (pinfunction "25_25") (pintype "input"))
    )
    (net (code "64") (name "D63") (class "Default")
      (node (ref "H11") (pin "27") (pinfunction "27_27") (pintype "input"))
    )
    (net (code "65") (name "D64") (class "Default")
      (node (ref "H11") (pin "29") (pinfunction "29_29") (pintype "input"))
      (node (ref "H8") (pin "17") (pinfunction "17_17") (pintype "input"))
    )
    (net (code "66") (name "D65") (class "Default")
      (node (ref "H11") (pin "30") (pinfunction "30_30") (pintype "input"))
      (node (ref "H8") (pin "8") (pinfunction "8_8") (pintype "input"))
    )
    (net (code "67") (name "D66") (class "Default")
      (node (ref "FPC3") (pin "11") (pinfunction "11_11") (pintype "unspecified"))
      (node (ref "H11") (pin "28") (pinfunction "28_28") (pintype "input"))
    )
    (net (code "68") (name "D67") (class "Default")
      (node (ref "FPC3") (pin "7") (pinfunction "7_7") (pintype "unspecified"))
      (node (ref "H11") (pin "26") (pinfunction "26_26") (pintype "input"))
    )
    (net (code "69") (name "D68") (class "Default")
      (node (ref "FPC3") (pin "5") (pinfunction "5_5") (pintype "unspecified"))
      (node (ref "H11") (pin "22") (pinfunction "22_22") (pintype "input"))
    )
    (net (code "70") (name "D69") (class "Default")
      (node (ref "H11") (pin "20") (pinfunction "20_20") (pintype "input"))
    )
    (net (code "71") (name "D70") (class "Default")
      (node (ref "H11") (pin "18") (pinfunction "18_18") (pintype "input"))
    )
    (net (code "72") (name "D71") (class "Default")
      (node (ref "H11") (pin "16") (pinfunction "16_16") (pintype "input"))
      (node (ref "H3") (pin "15") (pinfunction "15_15") (pintype "input"))
      (node (ref "J6") (pin "15") (pinfunction "15_15") (pintype "input"))
    )
    (net (code "73") (name "D72") (class "Default")
      (node (ref "H11") (pin "14") (pinfunction "14_14") (pintype "input"))
      (node (ref "H3") (pin "13") (pinfunction "13_13") (pintype "input"))
      (node (ref "J6") (pin "13") (pinfunction "13_13") (pintype "input"))
    )
    (net (code "74") (name "DAC1_O") (class "Default")
      (node (ref "C16") (pin "2") (pinfunction "2_2") (pintype "unspecified"))
      (node (ref "J5") (pin "1") (pinfunction "1_1") (pintype "unspecified"))
      (node (ref "J5") (pin "2") (pinfunction "2_2") (pintype "unspecified"))
      (node (ref "U16") (pin "1") (pinfunction "VOUT_1") (pintype "unspecified"))
    )
    (net (code "75") (name "Dxx") (class "Default")
      (node (ref "R10") (pin "1") (pinfunction "1_1") (pintype "unspecified"))
    )
    (net (code "76") (name "GND") (class "Default")
      (node (ref "A2") (pin "1") (pinfunction "1_1") (pintype "unspecified"))
      (node (ref "A2") (pin "2") (pinfunction "2_2") (pintype "unspecified"))
      (node (ref "BUZZER1") (pin "2") (pinfunction "2_2") (pintype "unspecified"))
      (node (ref "BUZZER1") (pin "3") (pinfunction "3_3") (pintype "unspecified"))
      (node (ref "BUZZER1") (pin "4") (pinfunction "4_4") (pintype "unspecified"))
      (node (ref "C1") (pin "1") (pinfunction "1_1") (pintype "unspecified"))
      (node (ref "C10") (pin "2") (pinfunction "2_2") (pintype "unspecified"))
      (node (ref "C11") (pin "1") (pinfunction "1_1") (pintype "unspecified"))
      (node (ref "C12") (pin "1") (pinfunction "1_1") (pintype "unspecified"))
      (node (ref "C13") (pin "1") (pinfunction "1_1") (pintype "unspecified"))
      (node (ref "C14") (pin "1") (pinfunction "1_1") (pintype "unspecified"))
      (node (ref "C15") (pin "1") (pinfunction "1_1") (pintype "unspecified"))
      (node (ref "C16") (pin "1") (pinfunction "1_1") (pintype "unspecified"))
      (node (ref "C17") (pin "1") (pinfunction "1_1") (pintype "unspecified"))
      (node (ref "C2") (pin "1") (pinfunction "1_1") (pintype "unspecified"))
      (node (ref "C3") (pin "1") (pinfunction "1_1") (pintype "unspecified"))
      (node (ref "C4") (pin "1") (pinfunction "1_1") (pintype "unspecified"))
      (node (ref "C5") (pin "1") (pinfunction "1_1") (pintype "unspecified"))
      (node (ref "C6") (pin "1") (pinfunction "1_1") (pintype "unspecified"))
      (node (ref "C7") (pin "1") (pinfunction "1_1") (pintype "unspecified"))
      (node (ref "CARD1") (pin "6") (pinfunction "VSS_6") (pintype "unspecified"))
      (node (ref "D2") (pin "1") (pinfunction "1_1") (pintype "unspecified"))
      (node (ref "D2") (pin "2") (pinfunction "2_2") (pintype "unspecified"))
      (node (ref "D6") (pin "2") (pinfunction "2_2") (pintype "unspecified"))
      (node (ref "D7") (pin "2") (pinfunction "2_2") (pintype "unspecified"))
      (node (ref "FPC3") (pin "17") (pinfunction "17_17") (pintype "unspecified"))
      (node (ref "FPC3") (pin "20") (pinfunction "20_20") (pintype "unspecified"))
      (node (ref "FPC3") (pin "6") (pinfunction "6_6") (pintype "unspecified"))
      (node (ref "H1") (pin "8") (pinfunction "8_8") (pintype "input"))
      (node (ref "H10") (pin "1") (pinfunction "1_1") (pintype "unspecified"))
      (node (ref "H11") (pin "11") (pinfunction "11_11") (pintype "input"))
      (node (ref "H11") (pin "24") (pinfunction "24_24") (pintype "input"))
      (node (ref "H12") (pin "18") (pinfunction "18_18") (pintype "input"))
      (node (ref "H12") (pin "21") (pinfunction "21_21") (pintype "input"))
      (node (ref "H12") (pin "28") (pinfunction "28_28") (pintype "input"))
      (node (ref "H12") (pin "6") (pinfunction "6_6") (pintype "input"))
      (node (ref "H13") (pin "3") (pinfunction "3_3") (pintype "input"))
      (node (ref "H14") (pin "1") (pinfunction "1_1") (pintype "unspecified"))
      (node (ref "H2") (pin "11") (pinfunction "11_11") (pintype "input"))
      (node (ref "H2") (pin "13") (pinfunction "13_13") (pintype "input"))
      (node (ref "H3") (pin "12") (pinfunction "12_12") (pintype "input"))
      (node (ref "H4") (pin "17") (pinfunction "17_17") (pintype "input"))
      (node (ref "H4") (pin "22") (pinfunction "22_22") (pintype "input"))
      (node (ref "H4") (pin "27") (pinfunction "27_27") (pintype "input"))
      (node (ref "H4") (pin "5") (pinfunction "5_5") (pintype "input"))
      (node (ref "H5") (pin "1") (pinfunction "1_1") (pintype "unspecified"))
      (node (ref "H5") (pin "2") (pinfunction "2_2") (pintype "unspecified"))
      (node (ref "H5") (pin "3") (pinfunction "3_3") (pintype "unspecified"))
      (node (ref "H6") (pin "1") (pinfunction "1_1") (pintype "unspecified"))
      (node (ref "H7") (pin "2") (pinfunction "2_2") (pintype "unspecified"))
      (node (ref "H8") (pin "1") (pinfunction "1_1") (pintype "input"))
      (node (ref "H8") (pin "19") (pinfunction "19_19") (pintype "input"))
      (node (ref "J1") (pin "7") (pinfunction "7_7") (pintype "unspecified"))
      (node (ref "J10") (pin "2") (pinfunction "2_2") (pintype "unspecified"))
      (node (ref "J13") (pin "1") (pinfunction "1_1") (pintype "unspecified"))
      (node (ref "J2") (pin "8") (pinfunction "8_8") (pintype "unspecified"))
      (node (ref "J3") (pin "12") (pinfunction "12_12") (pintype "input"))
      (node (ref "J3") (pin "14") (pinfunction "14_14") (pintype "input"))
      (node (ref "J4") (pin "11") (pinfunction "11_11") (pintype "input"))
      (node (ref "J4") (pin "13") (pinfunction "13_13") (pintype "input"))
      (node (ref "J6") (pin "12") (pinfunction "12_12") (pintype "input"))
      (node (ref "J8") (pin "17") (pinfunction "17_17") (pintype "input"))
      (node (ref "J8") (pin "22") (pinfunction "22_22") (pintype "input"))
      (node (ref "J8") (pin "27") (pinfunction "27_27") (pintype "input"))
      (node (ref "J8") (pin "5") (pinfunction "5_5") (pintype "input"))
      (node (ref "J9") (pin "1") (pinfunction "1_1") (pintype "unspecified"))
      (node (ref "J9") (pin "2") (pinfunction "2_2") (pintype "unspecified"))
      (node (ref "J9") (pin "3") (pinfunction "3_3") (pintype "unspecified"))
      (node (ref "MIC1") (pin "2") (pinfunction "GND_2") (pintype "unspecified"))
      (node (ref "MIC1") (pin "3") (pinfunction "GND_3") (pintype "unspecified"))
      (node (ref "NRST") (pin "1") (pinfunction "1_1") (pintype "unspecified"))
      (node (ref "NRST") (pin "2") (pinfunction "2_2") (pintype "unspecified"))
      (node (ref "NRST2") (pin "1") (pinfunction "1_1") (pintype "unspecified"))
      (node (ref "NRST2") (pin "2") (pinfunction "2_2") (pintype "unspecified"))
      (node (ref "R21") (pin "1") (pinfunction "1_1") (pintype "unspecified"))
      (node (ref "R23") (pin "2") (pinfunction "2_2") (pintype "unspecified"))
      (node (ref "SPK1") (pin "3") (pinfunction "3_3") (pintype "unspecified"))
      (node (ref "SPK1") (pin "4") (pinfunction "4_4") (pintype "unspecified"))
      (node (ref "U1") (pin "3") (pinfunction "GND_3") (pintype "unspecified"))
      (node (ref "U16") (pin "2") (pinfunction "VSS_2") (pintype "unspecified"))
      (node (ref "U16") (pin "6") (pinfunction "A0_6") (pintype "unspecified"))
      (node (ref "U2") (pin "1") (pinfunction "GND_1") (pintype "unspecified"))
      (node (ref "U3") (pin "1") (pinfunction "GND_1") (pintype "unspecified"))
      (node (ref "U4") (pin "2") (pinfunction "A1_2") (pintype "unspecified"))
      (node (ref "U4") (pin "3") (pinfunction "A2_3") (pintype "unspecified"))
      (node (ref "U4") (pin "4") (pinfunction "GND_4") (pintype "unspecified"))
      (node (ref "U4") (pin "7") (pinfunction "WP_7") (pintype "unspecified"))
      (node (ref "U5") (pin "4") (pinfunction "GND_4") (pintype "unspecified"))
      (node (ref "U6") (pin "4") (pinfunction "VEE/GND_4") (pintype "unspecified"))
      (node (ref "U7") (pin "5") (pinfunction "VSS/VSSA_5") (pintype "unspecified"))
      (node (ref "U8") (pin "7") (pinfunction "GND_7") (pintype "unspecified"))
      (node (ref "U9") (pin "4") (pinfunction "GND_4") (pintype "unspecified"))
      (node (ref "X1") (pin "2") (pinfunction "GND_2") (pintype "unspecified"))
    )
    (net (code "77") (name "IOREF") (class "Default")
      (node (ref "H2") (pin "3") (pinfunction "3_3") (pintype "input"))
      (node (ref "J3") (pin "4") (pinfunction "4_4") (pintype "input"))
      (node (ref "J4") (pin "3") (pinfunction "3_3") (pintype "input"))
    )
    (net (code "78") (name "MISO") (class "Default")
      (node (ref "H1") (pin "12") (pinfunction "12_12") (pintype "input"))
      (node (ref "H6") (pin "7") (pinfunction "7_7") (pintype "unspecified"))
      (node (ref "J1") (pin "11") (pinfunction "11_11") (pintype "unspecified"))
      (node (ref "J2") (pin "12") (pinfunction "12_12") (pintype "unspecified"))
      (node (ref "U7") (pin "28") (pinfunction "PB4_28") (pintype "unspecified"))
    )
    (net (code "79") (name "MISO2") (class "Default")
      (node (ref "H1") (pin "19") (pinfunction "19_19") (pintype "input"))
      (node (ref "H10") (pin "7") (pinfunction "7_7") (pintype "unspecified"))
      (node (ref "J1") (pin "20") (pinfunction "20_20") (pintype "unspecified"))
      (node (ref "J2") (pin "19") (pinfunction "19_19") (pintype "unspecified"))
      (node (ref "U7") (pin "30") (pinfunction "PB6_30") (pintype "unspecified"))
    )
    (net (code "80") (name "MOSI") (class "Default")
      (node (ref "H1") (pin "14") (pinfunction "14_14") (pintype "input"))
      (node (ref "H14") (pin "4") (pinfunction "4_4") (pintype "unspecified"))
      (node (ref "H6") (pin "6") (pinfunction "6_6") (pintype "unspecified"))
      (node (ref "J1") (pin "13") (pinfunction "13_13") (pintype "unspecified"))
      (node (ref "J2") (pin "14") (pinfunction "14_14") (pintype "unspecified"))
      (node (ref "U7") (pin "29") (pinfunction "PB5_29") (pintype "unspecified"))
    )
    (net (code "81") (name "MOSI2") (class "Default")
      (node (ref "H1") (pin "13") (pinfunction "13_13") (pintype "input"))
      (node (ref "H10") (pin "6") (pinfunction "6_6") (pintype "unspecified"))
      (node (ref "J1") (pin "14") (pinfunction "14_14") (pintype "unspecified"))
      (node (ref "J2") (pin "13") (pinfunction "13_13") (pintype "unspecified"))
      (node (ref "U7") (pin "31") (pinfunction "PB7_31") (pintype "unspecified"))
    )
    (net (code "82") (name "NRST") (class "Default")
      (node (ref "FPC3") (pin "10") (pinfunction "10_10") (pintype "unspecified"))
      (node (ref "H14") (pin "5") (pinfunction "5_5") (pintype "unspecified"))
      (node (ref "H2") (pin "5") (pinfunction "5_5") (pintype "input"))
      (node (ref "J3") (pin "6") (pinfunction "6_6") (pintype "input"))
      (node (ref "J4") (pin "5") (pinfunction "5_5") (pintype "input"))
      (node (ref "NRST") (pin "3") (pinfunction "3_3") (pintype "unspecified"))
      (node (ref "NRST") (pin "4") (pinfunction "4_4") (pintype "unspecified"))
    )
    (net (code "83") (name "NRST2") (class "Default")
      (node (ref "J10") (pin "1") (pinfunction "1_1") (pintype "unspecified"))
      (node (ref "NRST2") (pin "3") (pinfunction "3_3") (pintype "unspecified"))
      (node (ref "NRST2") (pin "4") (pinfunction "4_4") (pintype "unspecified"))
      (node (ref "U7") (pin "6") (pinfunction "PF2-NRST_6") (pintype "unspecified"))
    )
    (net (code "84") (name "NSS") (class "Default")
      (node (ref "H1") (pin "16") (pinfunction "16_16") (pintype "input"))
      (node (ref "H6") (pin "4") (pinfunction "4_4") (pintype "unspecified"))
      (node (ref "J1") (pin "15") (pinfunction "15_15") (pintype "unspecified"))
      (node (ref "J14") (pin "1") (pinfunction "1_1") (pintype "unspecified"))
      (node (ref "J2") (pin "16") (pinfunction "16_16") (pintype "unspecified"))
      (node (ref "U7") (pin "26") (pinfunction "PA15_26") (pintype "unspecified"))
    )
    (net (code "85") (name "NSS2") (class "Default")
      (node (ref "C7") (pin "2") (pinfunction "2_2") (pintype "unspecified"))
      (node (ref "H1") (pin "17") (pinfunction "17_17") (pintype "input"))
      (node (ref "H10") (pin "4") (pinfunction "4_4") (pintype "unspecified"))
      (node (ref "J1") (pin "18") (pinfunction "18_18") (pintype "unspecified"))
      (node (ref "J2") (pin "17") (pinfunction "17_17") (pintype "unspecified"))
      (node (ref "U7") (pin "1") (pinfunction "PB9_1") (pintype "unspecified"))
    )
    (net (code "86") (name "Net-(C8-Pad2)") (class "Default")
      (node (ref "C8") (pin "2") (pinfunction "2_2") (pintype "unspecified"))
      (node (ref "R18") (pin "1") (pinfunction "1_1") (pintype "unspecified"))
    )
    (net (code "87") (name "Net-(C9-Pad2)") (class "Default")
      (node (ref "C9") (pin "2") (pinfunction "2_2") (pintype "unspecified"))
      (node (ref "R7") (pin "1") (pinfunction "1_1") (pintype "unspecified"))
    )
    (net (code "88") (name "Net-(C11-Pad2)") (class "Default")
      (node (ref "C11") (pin "2") (pinfunction "2_2") (pintype "unspecified"))
      (node (ref "R10") (pin "2") (pinfunction "2_2") (pintype "unspecified"))
      (node (ref "R11") (pin "1") (pinfunction "1_1") (pintype "unspecified"))
    )
    (net (code "89") (name "Net-(C12-Pad2)") (class "Default")
      (node (ref "C12") (pin "2") (pinfunction "2_2") (pintype "unspecified"))
      (node (ref "J11") (pin "5") (pinfunction "5_5") (pintype "input"))
      (node (ref "J11") (pin "6") (pinfunction "6_6") (pintype "input"))
      (node (ref "R11") (pin "2") (pinfunction "2_2") (pintype "unspecified"))
    )
    (net (code "90") (name "Net-(D6-Pad1)") (class "Default")
      (node (ref "D6") (pin "1") (pinfunction "1_1") (pintype "unspecified"))
      (node (ref "R1") (pin "1") (pinfunction "1_1") (pintype "unspecified"))
    )
    (net (code "91") (name "Net-(D7-Pad1)") (class "Default")
      (node (ref "D7") (pin "1") (pinfunction "1_1") (pintype "unspecified"))
      (node (ref "R2") (pin "1") (pinfunction "1_1") (pintype "unspecified"))
    )
    (net (code "92") (name "Net-(Q2-B)") (class "Default")
      (node (ref "Q2") (pin "1") (pinfunction "B_1") (pintype "unspecified"))
      (node (ref "R17") (pin "1") (pinfunction "1_1") (pintype "unspecified"))
      (node (ref "R6") (pin "2") (pinfunction "2_2") (pintype "unspecified"))
    )
    (net (code "93") (name "Net-(U6-IN1+)") (class "Default")
      (node (ref "R20") (pin "2") (pinfunction "2_2") (pintype "unspecified"))
      (node (ref "R21") (pin "2") (pinfunction "2_2") (pintype "unspecified"))
      (node (ref "U6") (pin "3") (pinfunction "IN1+_3") (pintype "unspecified"))
    )
    (net (code "94") (name "Net-(U6-IN1-)") (class "Default")
      (node (ref "R18") (pin "2") (pinfunction "2_2") (pintype "unspecified"))
      (node (ref "R19") (pin "2") (pinfunction "2_2") (pintype "unspecified"))
      (node (ref "U6") (pin "2") (pinfunction "IN1-_2") (pintype "unspecified"))
    )
    (net (code "95") (name "Net-(U6-IN2+)") (class "Default")
      (node (ref "H13") (pin "2") (pinfunction "2_2") (pintype "input"))
      (node (ref "U6") (pin "5") (pinfunction "IN2+_5") (pintype "unspecified"))
    )
    (net (code "96") (name "Net-(U6-IN2-)") (class "Default")
      (node (ref "H13") (pin "1") (pinfunction "1_1") (pintype "input"))
      (node (ref "U6") (pin "6") (pinfunction "IN2-_6") (pintype "unspecified"))
      (node (ref "U6") (pin "7") (pinfunction "OUT2_7") (pintype "unspecified"))
    )
    (net (code "97") (name "Net-(U6-OUT1)") (class "Default")
      (node (ref "R19") (pin "1") (pinfunction "1_1") (pintype "unspecified"))
      (node (ref "R22") (pin "1") (pinfunction "1_1") (pintype "unspecified"))
      (node (ref "U6") (pin "1") (pinfunction "OUT1_1") (pintype "unspecified"))
    )
    (net (code "98") (name "Net-(U7-PC14-OSC32_IN)") (class "Default")
      (node (ref "U7") (pin "2") (pinfunction "PC14-OSC32_IN_2") (pintype "unspecified"))
      (node (ref "X1") (pin "3") (pinfunction "OUT_3") (pintype "unspecified"))
    )
    (net (code "99") (name "Net-(U8-+IN)") (class "Default")
      (node (ref "C10") (pin "1") (pinfunction "1_1") (pintype "unspecified"))
      (node (ref "U8") (pin "2") (pinfunction "Bypass_2") (pintype "unspecified"))
      (node (ref "U8") (pin "3") (pinfunction "+IN_3") (pintype "unspecified"))
    )
    (net (code "100") (name "Net-(U8--IN)") (class "Default")
      (node (ref "R7") (pin "2") (pinfunction "2_2") (pintype "unspecified"))
      (node (ref "R8") (pin "1") (pinfunction "1_1") (pintype "unspecified"))
      (node (ref "U8") (pin "4") (pinfunction "-IN_4") (pintype "unspecified"))
    )
    (net (code "101") (name "Net-(U8-SD)") (class "Default")
      (node (ref "J13") (pin "2") (pinfunction "2_2") (pintype "unspecified"))
      (node (ref "R9") (pin "1") (pinfunction "1_1") (pintype "unspecified"))
      (node (ref "U8") (pin "1") (pinfunction "SD_1") (pintype "unspecified"))
    )
    (net (code "102") (name "QCLK") (class "Default")
      (node (ref "FPC3") (pin "12") (pinfunction "12_12") (pintype "unspecified"))
      (node (ref "H12") (pin "16") (pinfunction "16_16") (pintype "input"))
      (node (ref "H4") (pin "15") (pinfunction "15_15") (pintype "input"))
      (node (ref "J8") (pin "15") (pinfunction "15_15") (pintype "input"))
      (node (ref "U5") (pin "6") (pinfunction "CLK_6") (pintype "unspecified"))
      (node (ref "U9") (pin "6") (pinfunction "CLK_6") (pintype "unspecified"))
    )
    (net (code "103") (name "QCS") (class "Default")
      (node (ref "FPC3") (pin "18") (pinfunction "18_18") (pintype "unspecified"))
      (node (ref "H12") (pin "14") (pinfunction "14_14") (pintype "input"))
      (node (ref "H4") (pin "13") (pinfunction "13_13") (pintype "input"))
      (node (ref "J12") (pin "2") (pinfunction "2_2") (pintype "input"))
      (node (ref "J8") (pin "13") (pinfunction "13_13") (pintype "input"))
    )
    (net (code "104") (name "QCS_F1") (class "Default")
      (node (ref "J12") (pin "1") (pinfunction "1_1") (pintype "input"))
      (node (ref "R3") (pin "1") (pinfunction "1_1") (pintype "unspecified"))
      (node (ref "U5") (pin "1") (pinfunction "CS#_1") (pintype "unspecified"))
    )
    (net (code "105") (name "QCS_F2") (class "Default")
      (node (ref "J12") (pin "3") (pinfunction "3_3") (pintype "input"))
      (node (ref "R4") (pin "1") (pinfunction "1_1") (pintype "unspecified"))
      (node (ref "U9") (pin "1") (pinfunction "CS#_1") (pintype "unspecified"))
    )
    (net (code "106") (name "QD0") (class "Default")
      (node (ref "FPC3") (pin "16") (pinfunction "16_16") (pintype "unspecified"))
      (node (ref "H12") (pin "24") (pinfunction "24_24") (pintype "input"))
      (node (ref "H4") (pin "23") (pinfunction "23_23") (pintype "input"))
      (node (ref "J8") (pin "23") (pinfunction "23_23") (pintype "input"))
      (node (ref "U5") (pin "5") (pinfunction "DI(IO0)_5") (pintype "unspecified"))
    )
    (net (code "107") (name "QD1") (class "Default")
      (node (ref "FPC3") (pin "15") (pinfunction "15_15") (pintype "unspecified"))
      (node (ref "H12") (pin "22") (pinfunction "22_22") (pintype "input"))
      (node (ref "H4") (pin "21") (pinfunction "21_21") (pintype "input"))
      (node (ref "J8") (pin "21") (pinfunction "21_21") (pintype "input"))
      (node (ref "U5") (pin "2") (pinfunction "DO(IO1)_2") (pintype "unspecified"))
    )
    (net (code "108") (name "QD2") (class "Default")
      (node (ref "FPC3") (pin "14") (pinfunction "14_14") (pintype "unspecified"))
      (node (ref "H12") (pin "26") (pinfunction "26_26") (pintype "input"))
      (node (ref "H4") (pin "25") (pinfunction "25_25") (pintype "input"))
      (node (ref "J8") (pin "25") (pinfunction "25_25") (pintype "input"))
      (node (ref "U5") (pin "3") (pinfunction "WP#(IO2)_3") (pintype "unspecified"))
    )
    (net (code "109") (name "QD3") (class "Default")
      (node (ref "FPC3") (pin "13") (pinfunction "13_13") (pintype "unspecified"))
      (node (ref "H12") (pin "20") (pinfunction "20_20") (pintype "input"))
      (node (ref "H4") (pin "19") (pinfunction "19_19") (pintype "input"))
      (node (ref "J8") (pin "19") (pinfunction "19_19") (pintype "input"))
      (node (ref "U5") (pin "7") (pinfunction "HOLD#(IO3)_7") (pintype "unspecified"))
    )
    (net (code "110") (name "SCK") (class "Default")
      (node (ref "H1") (pin "10") (pinfunction "10_10") (pintype "input"))
      (node (ref "H14") (pin "3") (pinfunction "3_3") (pintype "unspecified"))
      (node (ref "H6") (pin "5") (pinfunction "5_5") (pintype "unspecified"))
      (node (ref "J1") (pin "9") (pinfunction "9_9") (pintype "unspecified"))
      (node (ref "J11") (pin "1") (pinfunction "1_1") (pintype "input"))
      (node (ref "J11") (pin "2") (pinfunction "2_2") (pintype "input"))
      (node (ref "J2") (pin "10") (pinfunction "10_10") (pintype "unspecified"))
      (node (ref "U7") (pin "27") (pinfunction "PB3_27") (pintype "unspecified"))
    )
    (net (code "111") (name "SCK2") (class "Default")
      (node (ref "H1") (pin "15") (pinfunction "15_15") (pintype "input"))
      (node (ref "H10") (pin "5") (pinfunction "5_5") (pintype "unspecified"))
      (node (ref "J1") (pin "16") (pinfunction "16_16") (pintype "unspecified"))
      (node (ref "J2") (pin "15") (pinfunction "15_15") (pintype "unspecified"))
      (node (ref "U7") (pin "32") (pinfunction "PB8_32") (pintype "unspecified"))
    )
    (net (code "112") (name "SCL") (class "Default")
      (node (ref "H1") (pin "2") (pinfunction "2_2") (pintype "input"))
      (node (ref "H8") (pin "3") (pinfunction "3_3") (pintype "input"))
      (node (ref "J1") (pin "1") (pinfunction "1_1") (pintype "unspecified"))
      (node (ref "J2") (pin "2") (pinfunction "2_2") (pintype "unspecified"))
      (node (ref "U16") (pin "5") (pinfunction "SCL_5") (pintype "unspecified"))
      (node (ref "U4") (pin "6") (pinfunction "SCL_6") (pintype "unspecified"))
      (node (ref "U7") (pin "22") (pinfunction "PA11[PA9]_22") (pintype "unspecified"))
    )
    (net (code "113") (name "SDA") (class "Default")
      (node (ref "H1") (pin "4") (pinfunction "4_4") (pintype "input"))
      (node (ref "H8") (pin "5") (pinfunction "5_5") (pintype "input"))
      (node (ref "J1") (pin "3") (pinfunction "3_3") (pintype "unspecified"))
      (node (ref "J2") (pin "4") (pinfunction "4_4") (pintype "unspecified"))
      (node (ref "U16") (pin "4") (pinfunction "SDA_4") (pintype "unspecified"))
      (node (ref "U4") (pin "5") (pinfunction "SDA_5") (pintype "unspecified"))
      (node (ref "U7") (pin "23") (pinfunction "PA12[PA10]_23") (pintype "unspecified"))
    )
    (net (code "114") (name "SPK1") (class "Default")
      (node (ref "J11") (pin "4") (pinfunction "4_4") (pintype "input"))
      (node (ref "R6") (pin "1") (pinfunction "1_1") (pintype "unspecified"))
    )
    (net (code "115") (name "SPK2") (class "Default")
      (node (ref "C9") (pin "1") (pinfunction "1_1") (pintype "unspecified"))
      (node (ref "J11") (pin "3") (pinfunction "3_3") (pintype "input"))
    )
    (net (code "116") (name "URX") (class "Default")
      (node (ref "H12") (pin "15") (pinfunction "15_15") (pintype "input"))
      (node (ref "H4") (pin "16") (pinfunction "16_16") (pintype "input"))
      (node (ref "H7") (pin "1") (pinfunction "1_1") (pintype "unspecified"))
      (node (ref "J8") (pin "16") (pinfunction "16_16") (pintype "input"))
      (node (ref "U7") (pin "19") (pinfunction "PA9_19") (pintype "unspecified"))
    )
    (net (code "117") (name "UTX") (class "Default")
      (node (ref "H12") (pin "13") (pinfunction "13_13") (pintype "input"))
      (node (ref "H4") (pin "14") (pinfunction "14_14") (pintype "input"))
      (node (ref "H7") (pin "8") (pinfunction "8_8") (pintype "unspecified"))
      (node (ref "J8") (pin "14") (pinfunction "14_14") (pintype "input"))
      (node (ref "U7") (pin "21") (pinfunction "PA10_21") (pintype "unspecified"))
    )
    (net (code "118") (name "VIN") (class "Default")
      (node (ref "H2") (pin "15") (pinfunction "15_15") (pintype "input"))
      (node (ref "J3") (pin "16") (pinfunction "16_16") (pintype "input"))
      (node (ref "J4") (pin "15") (pinfunction "15_15") (pintype "input"))
    )
    (net (code "119") (name "VO1") (class "Default")
      (node (ref "J15") (pin "3") (pinfunction "3_3") (pintype "input"))
      (node (ref "R8") (pin "2") (pinfunction "2_2") (pintype "unspecified"))
      (node (ref "SPK1") (pin "2") (pinfunction "-_2") (pintype "unspecified"))
      (node (ref "U8") (pin "5") (pinfunction "VO1_5") (pintype "unspecified"))
    )
    (net (code "120") (name "VO2") (class "Default")
      (node (ref "J15") (pin "1") (pinfunction "1_1") (pintype "input"))
      (node (ref "SPK1") (pin "1") (pinfunction "+_1") (pintype "unspecified"))
      (node (ref "U8") (pin "8") (pinfunction "VO2_8") (pintype "unspecified"))
    )
    (net (code "121") (name "VO3") (class "Default")
      (node (ref "BUZZER1") (pin "1") (pinfunction "1_1") (pintype "unspecified"))
      (node (ref "J15") (pin "2") (pinfunction "2_2") (pintype "input"))
      (node (ref "Q2") (pin "3") (pinfunction "C_3") (pintype "unspecified"))
    )
    (net (code "122") (name "unconnected-(CARD1-SHELL-Pad11)") (class "Default")
      (node (ref "CARD1") (pin "11") (pinfunction "SHELL_11") (pintype "unspecified+no_connect"))
    )
    (net (code "123") (name "unconnected-(CARD1-SW_CONTACT-Pad9)") (class "Default")
      (node (ref "CARD1") (pin "9") (pinfunction "SW_CONTACT_9") (pintype "unspecified+no_connect"))
    )
    (net (code "124") (name "unconnected-(CARD1-SW_SPRING-Pad10)") (class "Default")
      (node (ref "CARD1") (pin "10") (pinfunction "SW_SPRING_10") (pintype "unspecified+no_connect"))
    )
    (net (code "125") (name "unconnected-(FPC3-Pad1)") (class "Default")
      (node (ref "FPC3") (pin "1") (pinfunction "1_1") (pintype "unspecified"))
    )
    (net (code "126") (name "unconnected-(FPC3-Pad2)") (class "Default")
      (node (ref "FPC3") (pin "2") (pinfunction "2_2") (pintype "unspecified"))
    )
    (net (code "127") (name "unconnected-(FPC3-Pad3)") (class "Default")
      (node (ref "FPC3") (pin "3") (pinfunction "3_3") (pintype "unspecified"))
    )
    (net (code "128") (name "unconnected-(FPC3-Pad4)") (class "Default")
      (node (ref "FPC3") (pin "4") (pinfunction "4_4") (pintype "unspecified"))
    )
    (net (code "129") (name "unconnected-(FPC3-Pad21)") (class "Default")
      (node (ref "FPC3") (pin "21") (pinfunction "21_21") (pintype "unspecified"))
    )
    (net (code "130") (name "unconnected-(FPC3-Pad22)") (class "Default")
      (node (ref "FPC3") (pin "22") (pinfunction "22_22") (pintype "unspecified"))
    )
    (net (code "131") (name "unconnected-(H2-Pad1)") (class "Default")
      (node (ref "H2") (pin "1") (pinfunction "1_1") (pintype "input"))
    )
    (net (code "132") (name "unconnected-(H14-Pad8)") (class "Default")
      (node (ref "H14") (pin "8") (pinfunction "8_8") (pintype "unspecified"))
    )
    (net (code "133") (name "unconnected-(J3-Pad2)") (class "Default")
      (node (ref "J3") (pin "2") (pinfunction "2_2") (pintype "input"))
    )
    (net (code "134") (name "unconnected-(J4-Pad1)") (class "Default")
      (node (ref "J4") (pin "1") (pinfunction "1_1") (pintype "input"))
    )
    (net (code "135") (name "unconnected-(U7-PC15-OSC32_OUT-Pad3)") (class "Default")
      (node (ref "U7") (pin "3") (pinfunction "PC15-OSC32_OUT_3") (pintype "unspecified"))
    )
    (net (code "136") (name "unconnected-(X1-OE-Pad1)") (class "Default")
      (node (ref "X1") (pin "1") (pinfunction "OE_1") (pintype "unspecified"))
    )
  )
)
